# Simple_Motherboard.net
KiCad netlist of a schematic drawn in EAGLE
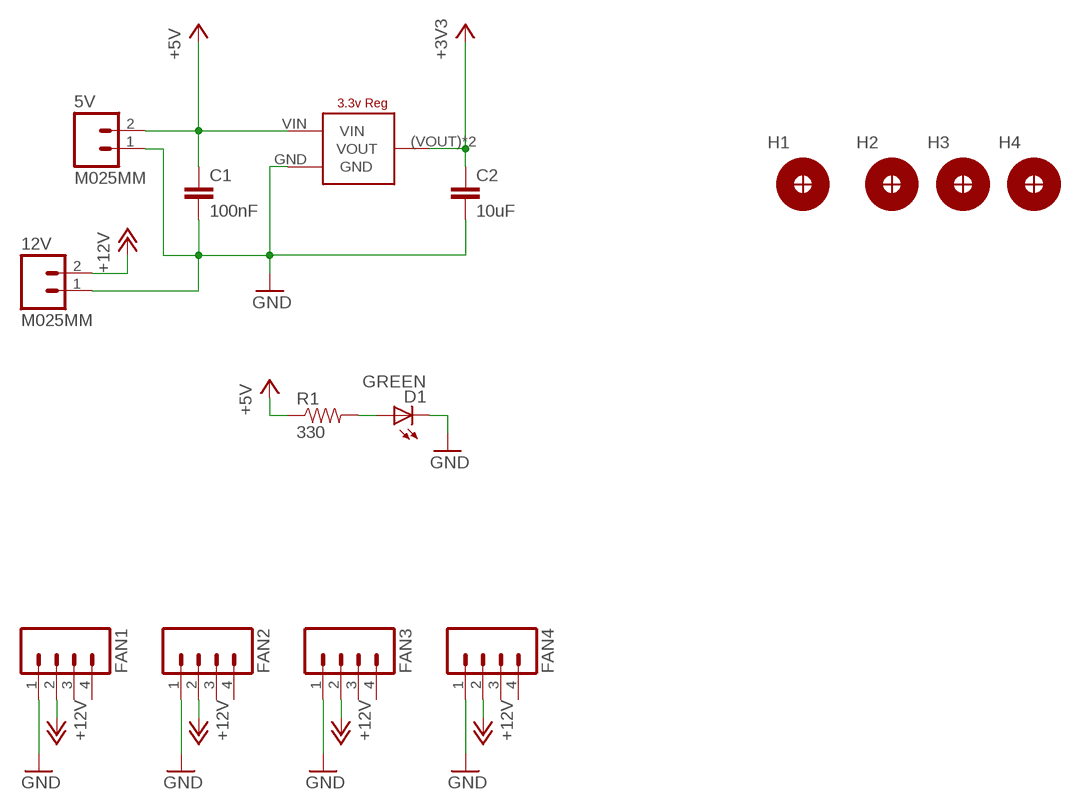
[diagram p0: schematic, sheet 1]
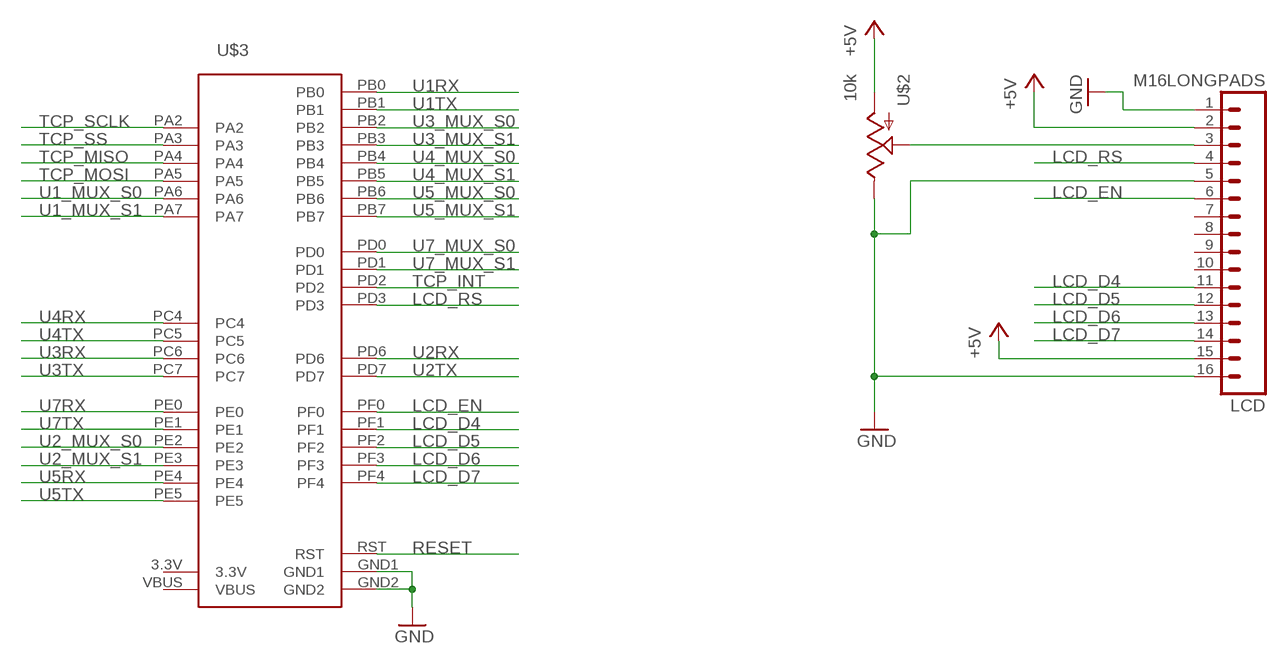
[diagram p1: schematic, sheet 2]
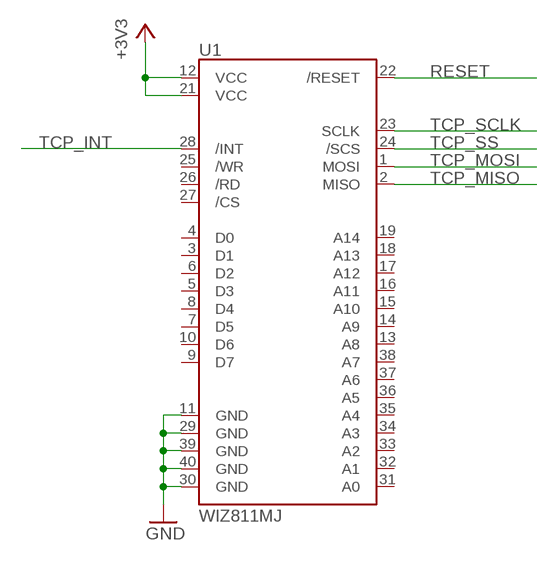
[diagram p2: schematic, sheet 3]
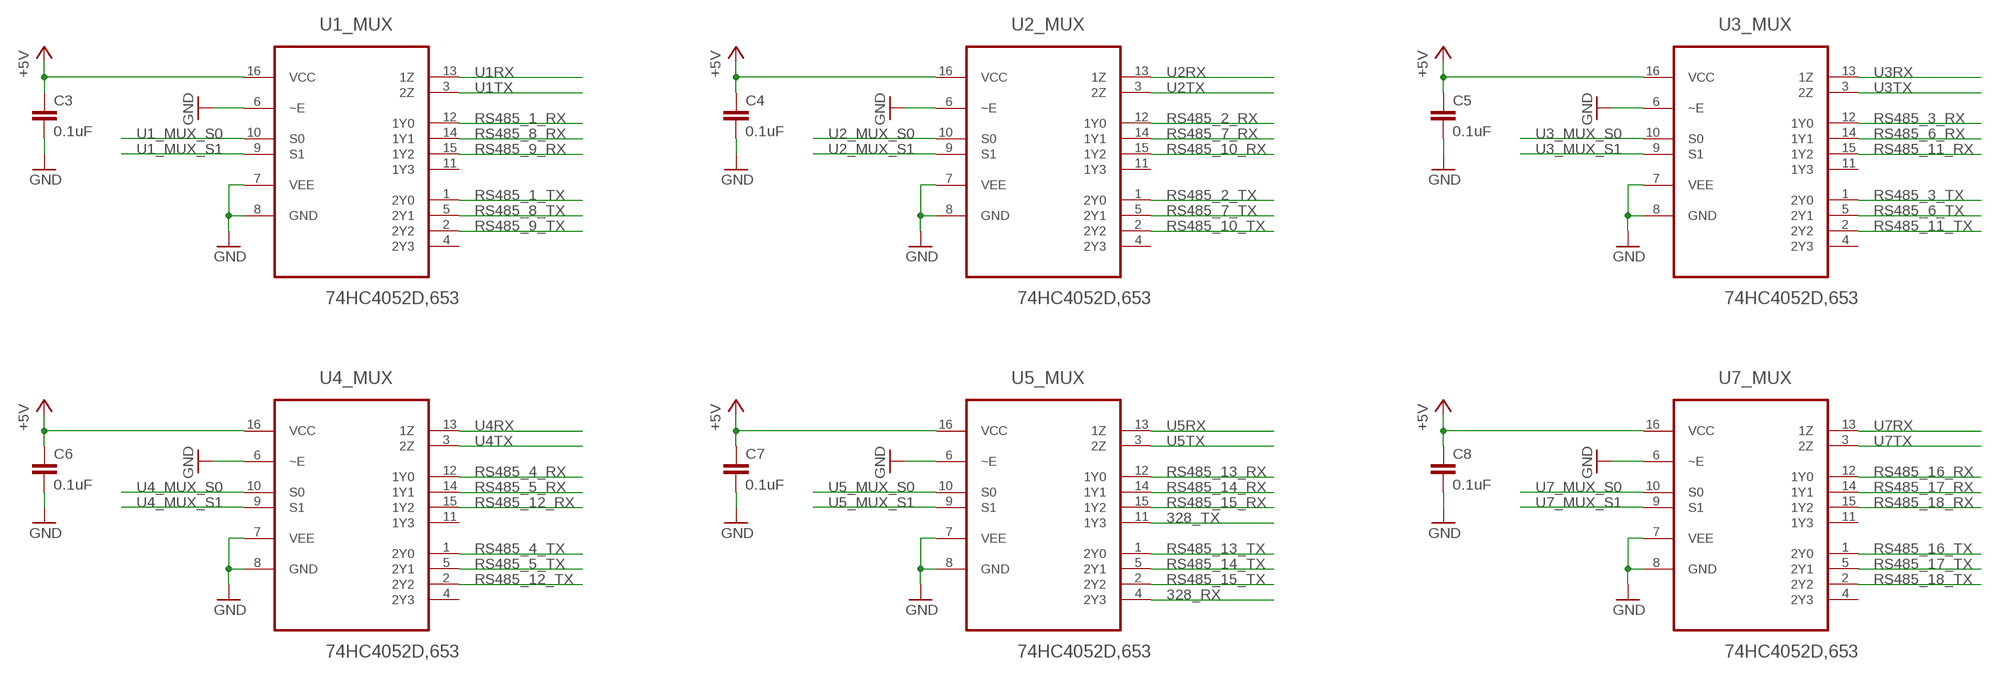
[diagram p3: schematic, sheet 4]
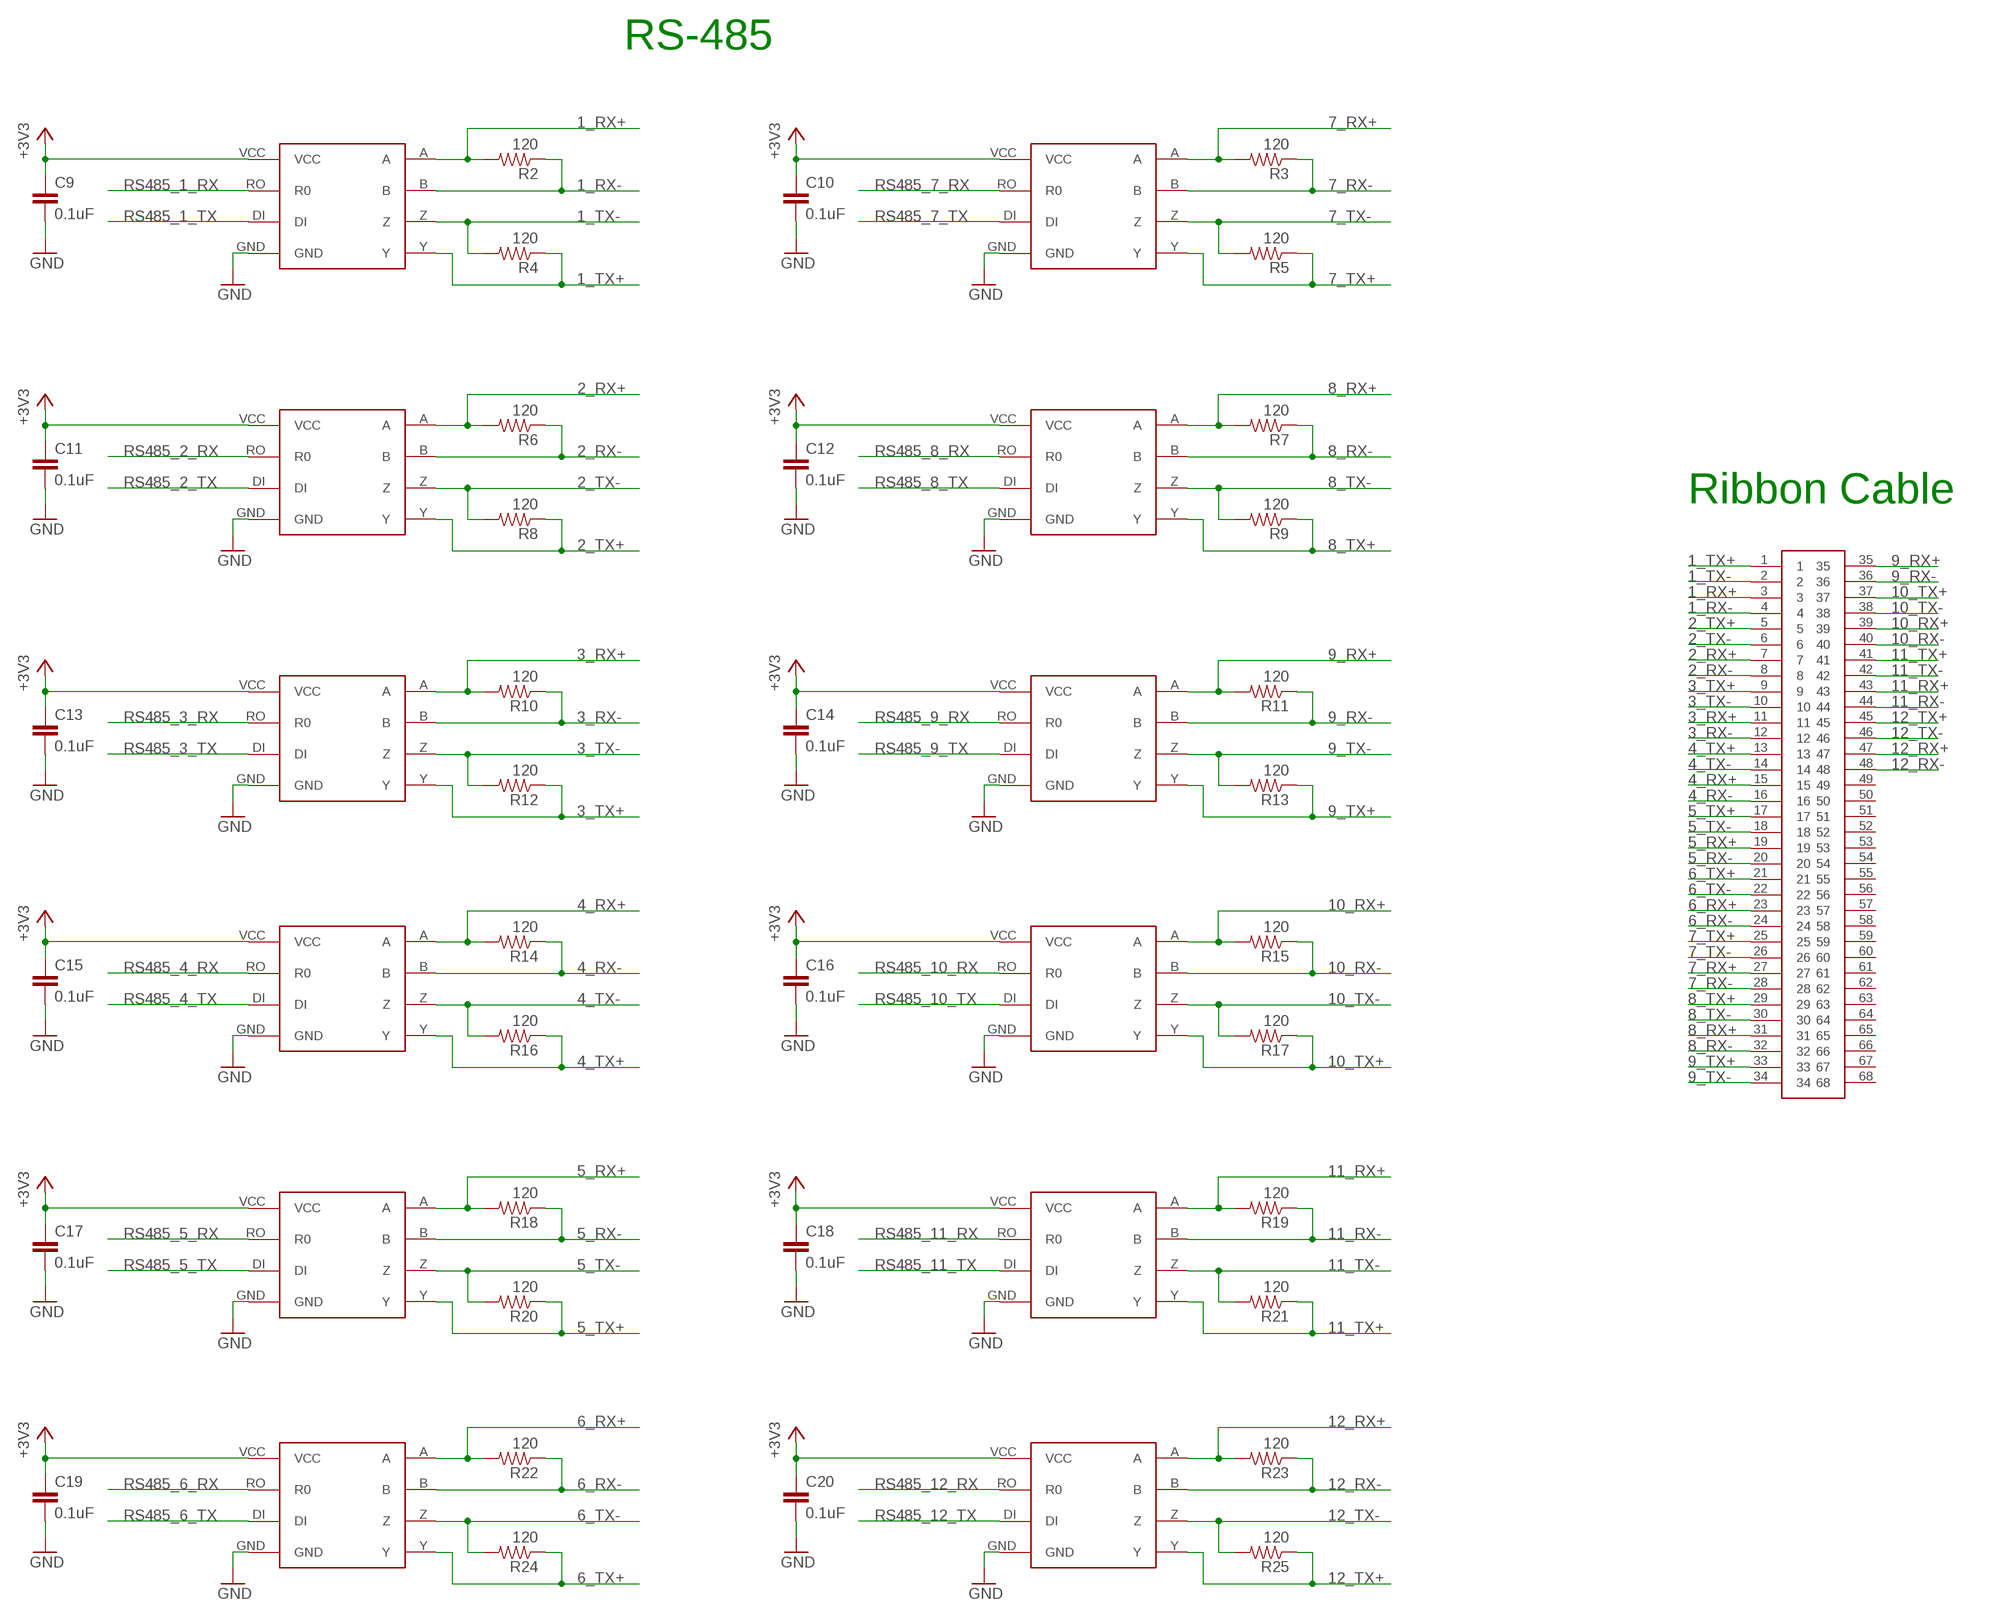
[diagram p4: schematic, sheet 5]
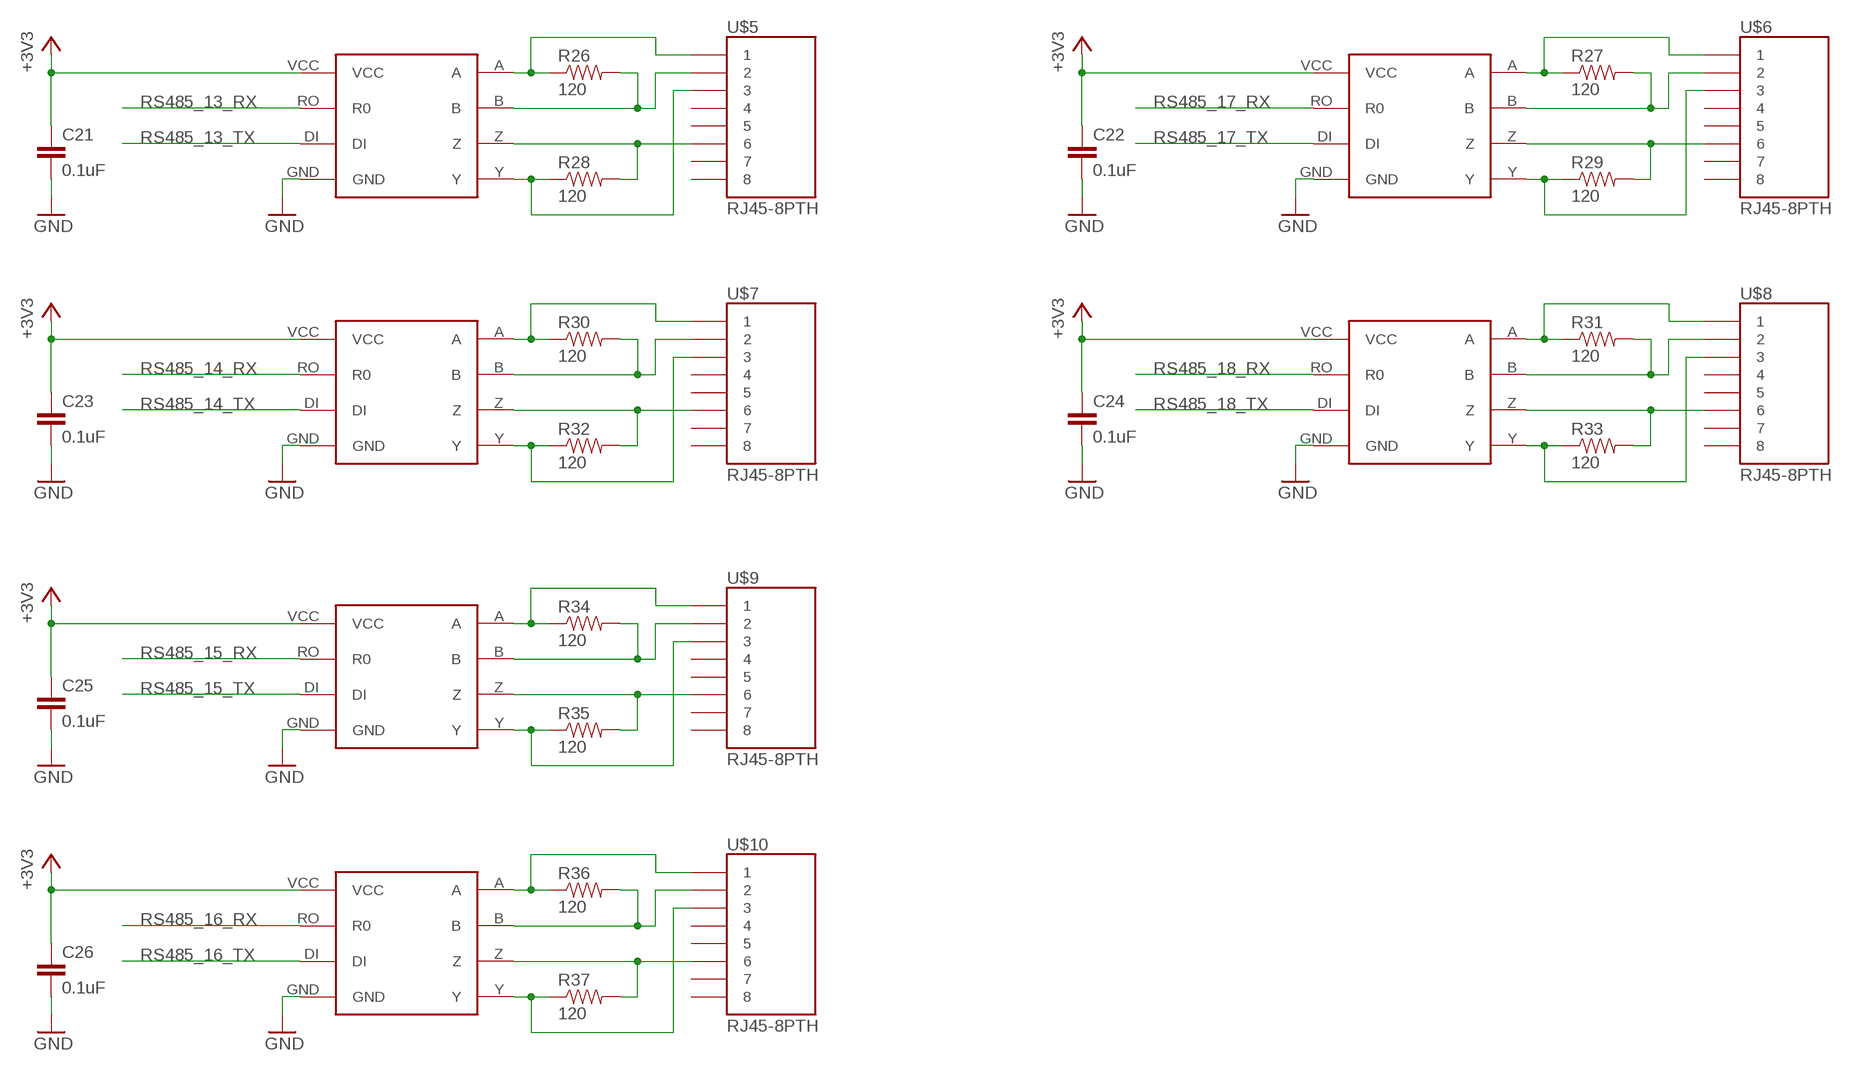
[diagram p5: schematic, sheet 6]
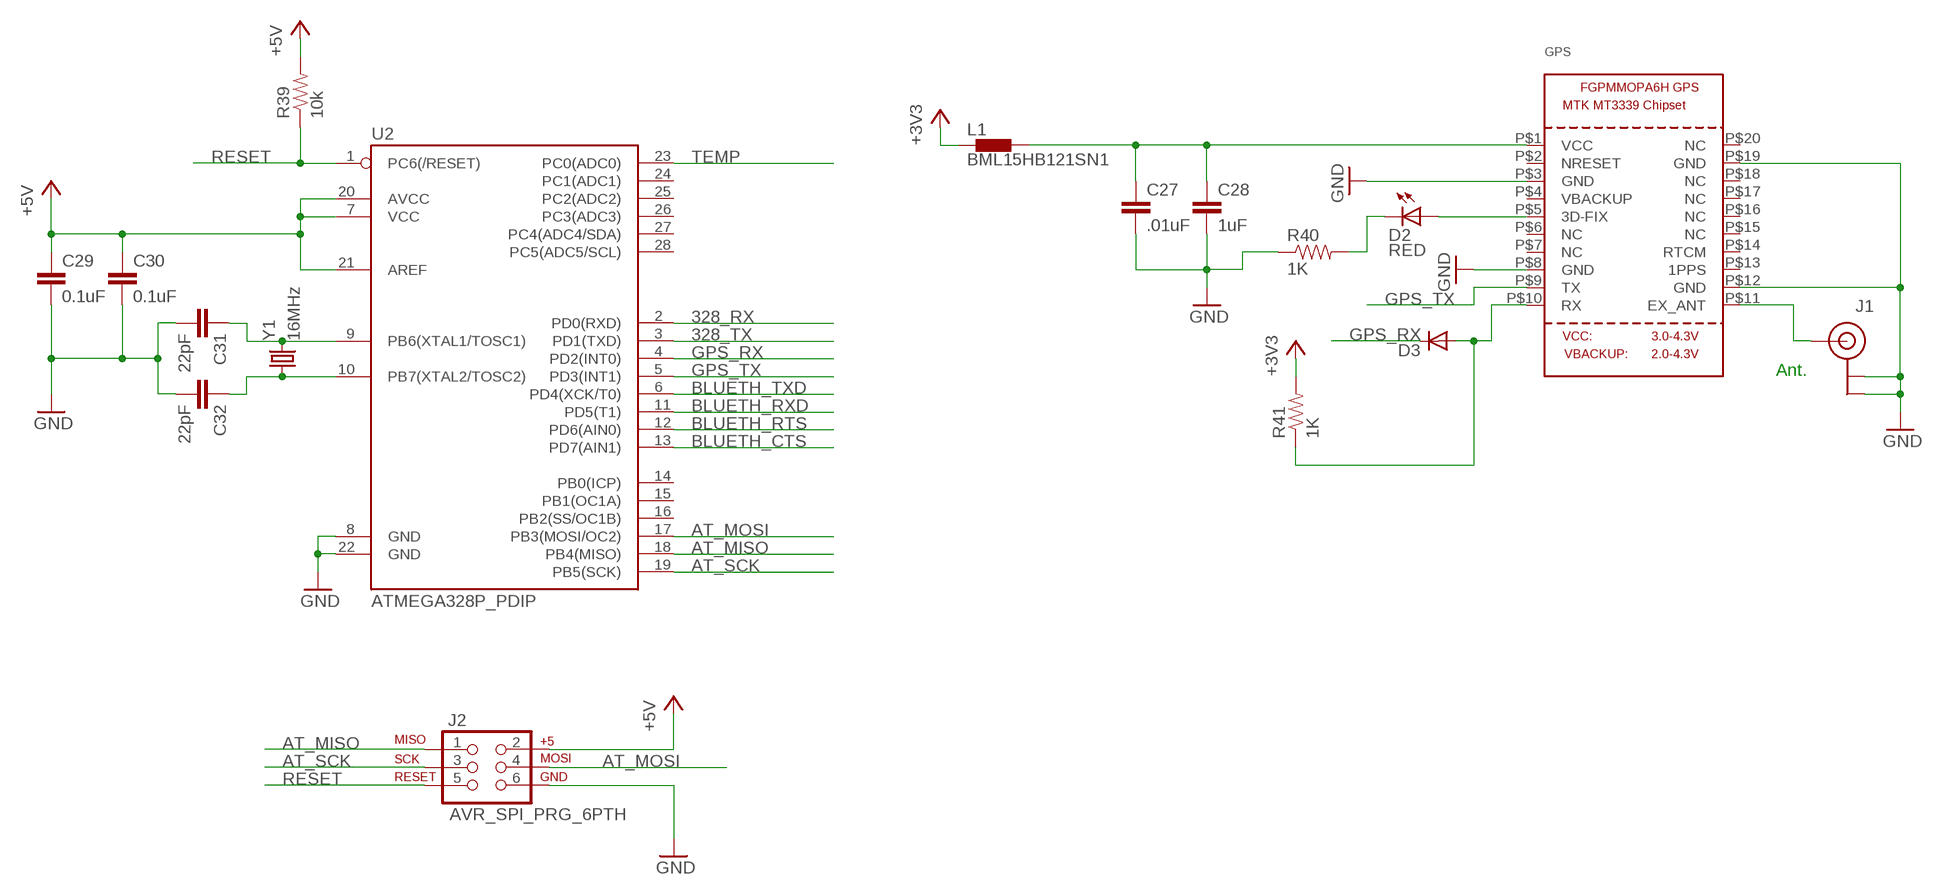
[diagram p6: schematic, sheet 7]

(export (version "E")
  (design (tool "Eeschema 10.0.6"))
  (components
    (comp (ref "C3")
      (value "0.1uF")
      (footprint "eagle-import:1206")
      (libsource (lib "eagle-import") (part "CAP1206"))
    )
    (comp (ref "C4")
      (value "0.1uF")
      (footprint "eagle-import:1206")
      (libsource (lib "eagle-import") (part "CAP1206"))
    )
    (comp (ref "C5")
      (value "0.1uF")
      (footprint "eagle-import:1206")
      (libsource (lib "eagle-import") (part "CAP1206"))
    )
    (comp (ref "C6")
      (value "0.1uF")
      (footprint "eagle-import:1206")
      (libsource (lib "eagle-import") (part "CAP1206"))
    )
    (comp (ref "C7")
      (value "0.1uF")
      (footprint "eagle-import:1206")
      (libsource (lib "eagle-import") (part "CAP1206"))
    )
    (comp (ref "C8")
      (value "0.1uF")
      (footprint "eagle-import:1206")
      (libsource (lib "eagle-import") (part "CAP1206"))
    )
    (comp (ref "U1_MUX")
      (value "74HC4052D,653")
      (footprint "eagle-import:SOIC127P600X175-16N")
      (libsource (lib "eagle-import") (part "74HC4052D,653"))
    )
    (comp (ref "U2_MUX")
      (value "74HC4052D,653")
      (footprint "eagle-import:SOIC127P600X175-16N")
      (libsource (lib "eagle-import") (part "74HC4052D,653"))
    )
    (comp (ref "U3_MUX")
      (value "74HC4052D,653")
      (footprint "eagle-import:SOIC127P600X175-16N")
      (libsource (lib "eagle-import") (part "74HC4052D,653"))
    )
    (comp (ref "U4_MUX")
      (value "74HC4052D,653")
      (footprint "eagle-import:SOIC127P600X175-16N")
      (libsource (lib "eagle-import") (part "74HC4052D,653"))
    )
    (comp (ref "U5_MUX")
      (value "74HC4052D,653")
      (footprint "eagle-import:SOIC127P600X175-16N")
      (libsource (lib "eagle-import") (part "74HC4052D,653"))
    )
    (comp (ref "U7_MUX")
      (value "74HC4052D,653")
      (footprint "eagle-import:SOIC127P600X175-16N")
      (libsource (lib "eagle-import") (part "74HC4052D,653"))
    )
    (comp (ref "LCD")
      (value "M16LONGPADS")
      (footprint "eagle-import:1X16_LONGPADS")
      (libsource (lib "eagle-import") (part "M16LONGPADS"))
    )
    (comp (ref "U$2")
      (value "10k")
      (footprint "eagle-import:3362U")
      (libsource (lib "eagle-import") (part "POT100K_3362U"))
    )
    (comp (ref "U$3")
      (value "STELLARIS-LAUNCHPADSTELLARIS-LAUNCHPAD-XL")
      (footprint "eagle-import:LAUNCHPAD-XL")
      (libsource (lib "eagle-import") (part "STELLARIS-LAUNCHPADSTELLARIS-LAUNCHPAD-XL"))
    )
    (comp (ref "U1")
      (value "WIZ811MJ")
      (footprint "eagle-import:WIZ811MJ")
      (libsource (lib "eagle-import") (part "WIZ811MJ"))
    )
    (comp (ref "C21")
      (value "0.1uF")
      (footprint "eagle-import:1206")
      (libsource (lib "eagle-import") (part "CAP1206"))
    )
    (comp (ref "C22")
      (value "0.1uF")
      (footprint "eagle-import:1206")
      (libsource (lib "eagle-import") (part "CAP1206"))
    )
    (comp (ref "C23")
      (value "0.1uF")
      (footprint "eagle-import:1206")
      (libsource (lib "eagle-import") (part "CAP1206"))
    )
    (comp (ref "C24")
      (value "0.1uF")
      (footprint "eagle-import:1206")
      (libsource (lib "eagle-import") (part "CAP1206"))
    )
    (comp (ref "C25")
      (value "0.1uF")
      (footprint "eagle-import:1206")
      (libsource (lib "eagle-import") (part "CAP1206"))
    )
    (comp (ref "C26")
      (value "0.1uF")
      (footprint "eagle-import:1206")
      (libsource (lib "eagle-import") (part "CAP1206"))
    )
    (comp (ref "R26")
      (value "120")
      (footprint "eagle-import:1206")
      (libsource (lib "eagle-import") (part "RESISTOR1206"))
    )
    (comp (ref "R27")
      (value "120")
      (footprint "eagle-import:1206")
      (libsource (lib "eagle-import") (part "RESISTOR1206"))
    )
    (comp (ref "R28")
      (value "120")
      (footprint "eagle-import:1206")
      (libsource (lib "eagle-import") (part "RESISTOR1206"))
    )
    (comp (ref "R29")
      (value "120")
      (footprint "eagle-import:1206")
      (libsource (lib "eagle-import") (part "RESISTOR1206"))
    )
    (comp (ref "R30")
      (value "120")
      (footprint "eagle-import:1206")
      (libsource (lib "eagle-import") (part "RESISTOR1206"))
    )
    (comp (ref "R31")
      (value "120")
      (footprint "eagle-import:1206")
      (libsource (lib "eagle-import") (part "RESISTOR1206"))
    )
    (comp (ref "R32")
      (value "120")
      (footprint "eagle-import:1206")
      (libsource (lib "eagle-import") (part "RESISTOR1206"))
    )
    (comp (ref "R33")
      (value "120")
      (footprint "eagle-import:1206")
      (libsource (lib "eagle-import") (part "RESISTOR1206"))
    )
    (comp (ref "R34")
      (value "120")
      (footprint "eagle-import:1206")
      (libsource (lib "eagle-import") (part "RESISTOR1206"))
    )
    (comp (ref "R35")
      (value "120")
      (footprint "eagle-import:1206")
      (libsource (lib "eagle-import") (part "RESISTOR1206"))
    )
    (comp (ref "R36")
      (value "120")
      (footprint "eagle-import:1206")
      (libsource (lib "eagle-import") (part "RESISTOR1206"))
    )
    (comp (ref "R37")
      (value "120")
      (footprint "eagle-import:1206")
      (libsource (lib "eagle-import") (part "RESISTOR1206"))
    )
    (comp (ref "RS-485-1")
      (value "MAX3077")
      (footprint "eagle-import:MAX3070E")
      (libsource (lib "eagle-import") (part "MAX3077"))
    )
    (comp (ref "RS-485-2")
      (value "MAX3077")
      (footprint "eagle-import:MAX3070E")
      (libsource (lib "eagle-import") (part "MAX3077"))
    )
    (comp (ref "RS-485-3")
      (value "MAX3077")
      (footprint "eagle-import:MAX3070E")
      (libsource (lib "eagle-import") (part "MAX3077"))
    )
    (comp (ref "RS-485-4")
      (value "MAX3077")
      (footprint "eagle-import:MAX3070E")
      (libsource (lib "eagle-import") (part "MAX3077"))
    )
    (comp (ref "RS-485-5")
      (value "MAX3077")
      (footprint "eagle-import:MAX3070E")
      (libsource (lib "eagle-import") (part "MAX3077"))
    )
    (comp (ref "RS-485-6")
      (value "MAX3077")
      (footprint "eagle-import:MAX3070E")
      (libsource (lib "eagle-import") (part "MAX3077"))
    )
    (comp (ref "U$5")
      (value "RJ45-8PTH")
      (footprint "eagle-import:RJ45-8")
      (libsource (lib "eagle-import") (part "RJ45-8PTH"))
    )
    (comp (ref "U$6")
      (value "RJ45-8PTH")
      (footprint "eagle-import:RJ45-8")
      (libsource (lib "eagle-import") (part "RJ45-8PTH"))
    )
    (comp (ref "U$7")
      (value "RJ45-8PTH")
      (footprint "eagle-import:RJ45-8")
      (libsource (lib "eagle-import") (part "RJ45-8PTH"))
    )
    (comp (ref "U$8")
      (value "RJ45-8PTH")
      (footprint "eagle-import:RJ45-8")
      (libsource (lib "eagle-import") (part "RJ45-8PTH"))
    )
    (comp (ref "U$9")
      (value "RJ45-8PTH")
      (footprint "eagle-import:RJ45-8")
      (libsource (lib "eagle-import") (part "RJ45-8PTH"))
    )
    (comp (ref "U$10")
      (value "RJ45-8PTH")
      (footprint "eagle-import:RJ45-8")
      (libsource (lib "eagle-import") (part "RJ45-8PTH"))
    )
    (comp (ref "C9")
      (value "0.1uF")
      (footprint "eagle-import:1206")
      (libsource (lib "eagle-import") (part "CAP1206"))
    )
    (comp (ref "C10")
      (value "0.1uF")
      (footprint "eagle-import:1206")
      (libsource (lib "eagle-import") (part "CAP1206"))
    )
    (comp (ref "C11")
      (value "0.1uF")
      (footprint "eagle-import:1206")
      (libsource (lib "eagle-import") (part "CAP1206"))
    )
    (comp (ref "C12")
      (value "0.1uF")
      (footprint "eagle-import:1206")
      (libsource (lib "eagle-import") (part "CAP1206"))
    )
    (comp (ref "C13")
      (value "0.1uF")
      (footprint "eagle-import:1206")
      (libsource (lib "eagle-import") (part "CAP1206"))
    )
    (comp (ref "C14")
      (value "0.1uF")
      (footprint "eagle-import:1206")
      (libsource (lib "eagle-import") (part "CAP1206"))
    )
    (comp (ref "C15")
      (value "0.1uF")
      (footprint "eagle-import:1206")
      (libsource (lib "eagle-import") (part "CAP1206"))
    )
    (comp (ref "C16")
      (value "0.1uF")
      (footprint "eagle-import:1206")
      (libsource (lib "eagle-import") (part "CAP1206"))
    )
    (comp (ref "C17")
      (value "0.1uF")
      (footprint "eagle-import:1206")
      (libsource (lib "eagle-import") (part "CAP1206"))
    )
    (comp (ref "C18")
      (value "0.1uF")
      (footprint "eagle-import:1206")
      (libsource (lib "eagle-import") (part "CAP1206"))
    )
    (comp (ref "C19")
      (value "0.1uF")
      (footprint "eagle-import:1206")
      (libsource (lib "eagle-import") (part "CAP1206"))
    )
    (comp (ref "C20")
      (value "0.1uF")
      (footprint "eagle-import:1206")
      (libsource (lib "eagle-import") (part "CAP1206"))
    )
    (comp (ref "R2")
      (value "120")
      (footprint "eagle-import:1206")
      (libsource (lib "eagle-import") (part "RESISTOR1206"))
    )
    (comp (ref "R3")
      (value "120")
      (footprint "eagle-import:1206")
      (libsource (lib "eagle-import") (part "RESISTOR1206"))
    )
    (comp (ref "R4")
      (value "120")
      (footprint "eagle-import:1206")
      (libsource (lib "eagle-import") (part "RESISTOR1206"))
    )
    (comp (ref "R5")
      (value "120")
      (footprint "eagle-import:1206")
      (libsource (lib "eagle-import") (part "RESISTOR1206"))
    )
    (comp (ref "R6")
      (value "120")
      (footprint "eagle-import:1206")
      (libsource (lib "eagle-import") (part "RESISTOR1206"))
    )
    (comp (ref "R7")
      (value "120")
      (footprint "eagle-import:1206")
      (libsource (lib "eagle-import") (part "RESISTOR1206"))
    )
    (comp (ref "R8")
      (value "120")
      (footprint "eagle-import:1206")
      (libsource (lib "eagle-import") (part "RESISTOR1206"))
    )
    (comp (ref "R9")
      (value "120")
      (footprint "eagle-import:1206")
      (libsource (lib "eagle-import") (part "RESISTOR1206"))
    )
    (comp (ref "R10")
      (value "120")
      (footprint "eagle-import:1206")
      (libsource (lib "eagle-import") (part "RESISTOR1206"))
    )
    (comp (ref "R11")
      (value "120")
      (footprint "eagle-import:1206")
      (libsource (lib "eagle-import") (part "RESISTOR1206"))
    )
    (comp (ref "R12")
      (value "120")
      (footprint "eagle-import:1206")
      (libsource (lib "eagle-import") (part "RESISTOR1206"))
    )
    (comp (ref "R13")
      (value "120")
      (footprint "eagle-import:1206")
      (libsource (lib "eagle-import") (part "RESISTOR1206"))
    )
    (comp (ref "R14")
      (value "120")
      (footprint "eagle-import:1206")
      (libsource (lib "eagle-import") (part "RESISTOR1206"))
    )
    (comp (ref "R15")
      (value "120")
      (footprint "eagle-import:1206")
      (libsource (lib "eagle-import") (part "RESISTOR1206"))
    )
    (comp (ref "R16")
      (value "120")
      (footprint "eagle-import:1206")
      (libsource (lib "eagle-import") (part "RESISTOR1206"))
    )
    (comp (ref "R17")
      (value "120")
      (footprint "eagle-import:1206")
      (libsource (lib "eagle-import") (part "RESISTOR1206"))
    )
    (comp (ref "R18")
      (value "120")
      (footprint "eagle-import:1206")
      (libsource (lib "eagle-import") (part "RESISTOR1206"))
    )
    (comp (ref "R19")
      (value "120")
      (footprint "eagle-import:1206")
      (libsource (lib "eagle-import") (part "RESISTOR1206"))
    )
    (comp (ref "R20")
      (value "120")
      (footprint "eagle-import:1206")
      (libsource (lib "eagle-import") (part "RESISTOR1206"))
    )
    (comp (ref "R21")
      (value "120")
      (footprint "eagle-import:1206")
      (libsource (lib "eagle-import") (part "RESISTOR1206"))
    )
    (comp (ref "R22")
      (value "120")
      (footprint "eagle-import:1206")
      (libsource (lib "eagle-import") (part "RESISTOR1206"))
    )
    (comp (ref "R23")
      (value "120")
      (footprint "eagle-import:1206")
      (libsource (lib "eagle-import") (part "RESISTOR1206"))
    )
    (comp (ref "R24")
      (value "120")
      (footprint "eagle-import:1206")
      (libsource (lib "eagle-import") (part "RESISTOR1206"))
    )
    (comp (ref "R25")
      (value "120")
      (footprint "eagle-import:1206")
      (libsource (lib "eagle-import") (part "RESISTOR1206"))
    )
    (comp (ref "RS_TRANS_1")
      (value "MAX3077")
      (footprint "eagle-import:MAX3070E")
      (libsource (lib "eagle-import") (part "MAX3077"))
    )
    (comp (ref "RS_TRANS_2")
      (value "MAX3077")
      (footprint "eagle-import:MAX3070E")
      (libsource (lib "eagle-import") (part "MAX3077"))
    )
    (comp (ref "RS_TRANS_3")
      (value "MAX3077")
      (footprint "eagle-import:MAX3070E")
      (libsource (lib "eagle-import") (part "MAX3077"))
    )
    (comp (ref "RS_TRANS_4")
      (value "MAX3077")
      (footprint "eagle-import:MAX3070E")
      (libsource (lib "eagle-import") (part "MAX3077"))
    )
    (comp (ref "RS_TRANS_5")
      (value "MAX3077")
      (footprint "eagle-import:MAX3070E")
      (libsource (lib "eagle-import") (part "MAX3077"))
    )
    (comp (ref "RS_TRANS_6")
      (value "MAX3077")
      (footprint "eagle-import:MAX3070E")
      (libsource (lib "eagle-import") (part "MAX3077"))
    )
    (comp (ref "RS_TRANS_7")
      (value "MAX3077")
      (footprint "eagle-import:MAX3070E")
      (libsource (lib "eagle-import") (part "MAX3077"))
    )
    (comp (ref "RS_TRANS_8")
      (value "MAX3077")
      (footprint "eagle-import:MAX3070E")
      (libsource (lib "eagle-import") (part "MAX3077"))
    )
    (comp (ref "RS_TRANS_9")
      (value "MAX3077")
      (footprint "eagle-import:MAX3070E")
      (libsource (lib "eagle-import") (part "MAX3077"))
    )
    (comp (ref "RS_TRANS_10")
      (value "MAX3077")
      (footprint "eagle-import:MAX3070E")
      (libsource (lib "eagle-import") (part "MAX3077"))
    )
    (comp (ref "RS_TRANS_11")
      (value "MAX3077")
      (footprint "eagle-import:MAX3070E")
      (libsource (lib "eagle-import") (part "MAX3077"))
    )
    (comp (ref "RS_TRANS_12")
      (value "MAX3077")
      (footprint "eagle-import:MAX3070E")
      (libsource (lib "eagle-import") (part "MAX3077"))
    )
    (comp (ref "U$4")
      (value "TB60050685100")
      (footprint "eagle-import:60050685100")
      (libsource (lib "eagle-import") (part "TB60050685100"))
    )
    (comp (ref "5V")
      (value "M025MM")
      (footprint "eagle-import:SCREWTERMINAL-5MM-2")
      (libsource (lib "eagle-import") (part "M025MM"))
    )
    (comp (ref "12V")
      (value "M025MM")
      (footprint "eagle-import:SCREWTERMINAL-5MM-2")
      (libsource (lib "eagle-import") (part "M025MM"))
    )
    (comp (ref "C1")
      (value "100nF")
      (footprint "eagle-import:1206")
      (libsource (lib "eagle-import") (part "CAP1206"))
    )
    (comp (ref "C2")
      (value "10uF")
      (footprint "eagle-import:1206")
      (libsource (lib "eagle-import") (part "CAP1206"))
    )
    (comp (ref "D1")
      (value "GREEN")
      (footprint "eagle-import:LED-1206")
      (libsource (lib "eagle-import") (part "LED-GREENLARGE"))
    )
    (comp (ref "FAN1")
      (value "M04LONGPADS")
      (footprint "eagle-import:1X04_LONGPADS")
      (libsource (lib "eagle-import") (part "M04LONGPADS"))
    )
    (comp (ref "FAN2")
      (value "M04LONGPADS")
      (footprint "eagle-import:1X04_LONGPADS")
      (libsource (lib "eagle-import") (part "M04LONGPADS"))
    )
    (comp (ref "FAN3")
      (value "M04LONGPADS")
      (footprint "eagle-import:1X04_LONGPADS")
      (libsource (lib "eagle-import") (part "M04LONGPADS"))
    )
    (comp (ref "FAN4")
      (value "M04LONGPADS")
      (footprint "eagle-import:1X04_LONGPADS")
      (libsource (lib "eagle-import") (part "M04LONGPADS"))
    )
    (comp (ref "H1")
      (value "H_MNTHOLE_#4")
      (footprint "eagle-import:H_MNTHOLE_#4")
      (libsource (lib "eagle-import") (part "H_MNTHOLE_#4"))
    )
    (comp (ref "H2")
      (value "H_MNTHOLE_#4")
      (footprint "eagle-import:H_MNTHOLE_#4")
      (libsource (lib "eagle-import") (part "H_MNTHOLE_#4"))
    )
    (comp (ref "H3")
      (value "H_MNTHOLE_#4")
      (footprint "eagle-import:H_MNTHOLE_#4")
      (libsource (lib "eagle-import") (part "H_MNTHOLE_#4"))
    )
    (comp (ref "H4")
      (value "H_MNTHOLE_#4")
      (footprint "eagle-import:H_MNTHOLE_#4")
      (libsource (lib "eagle-import") (part "H_MNTHOLE_#4"))
    )
    (comp (ref "R1")
      (value "330")
      (footprint "eagle-import:1206")
      (libsource (lib "eagle-import") (part "RESISTOR1206"))
    )
    (comp (ref "U$1")
      (value "LD1117")
      (footprint "eagle-import:LD1117SOT-223")
      (libsource (lib "eagle-import") (part "LD1117"))
    )
    (comp (ref "C27")
      (value ".01uF")
      (footprint "eagle-import:1206")
      (libsource (lib "eagle-import") (part "CAP1206"))
    )
    (comp (ref "C28")
      (value "1uF")
      (footprint "eagle-import:1206")
      (libsource (lib "eagle-import") (part "CAP1206"))
    )
    (comp (ref "C29")
      (value "0.1uF")
      (footprint "eagle-import:1206")
      (libsource (lib "eagle-import") (part "CAP1206"))
    )
    (comp (ref "C30")
      (value "0.1uF")
      (footprint "eagle-import:1206")
      (libsource (lib "eagle-import") (part "CAP1206"))
    )
    (comp (ref "C31")
      (value "22pF")
      (footprint "eagle-import:1206")
      (libsource (lib "eagle-import") (part "CAP1206"))
    )
    (comp (ref "C32")
      (value "22pF")
      (footprint "eagle-import:1206")
      (libsource (lib "eagle-import") (part "CAP1206"))
    )
    (comp (ref "D2")
      (value "RED")
      (footprint "eagle-import:LED-1206")
      (libsource (lib "eagle-import") (part "LED-RED1206"))
    )
    (comp (ref "D3")
      (value "DIODEHV")
      (footprint "eagle-import:DIODE-HV")
      (libsource (lib "eagle-import") (part "DIODEHV"))
    )
    (comp (ref "GPS")
      (value "GPS_FGPMMOPA6H")
      (footprint "eagle-import:FGPMMOPA6H")
      (libsource (lib "eagle-import") (part "GPS_FGPMMOPA6H"))
    )
    (comp (ref "J1")
      (value "U.FL")
      (footprint "eagle-import:U.FL")
      (libsource (lib "eagle-import") (part "U.FL"))
    )
    (comp (ref "J2")
      (value "AVR_SPI_PRG_6PTH")
      (footprint "eagle-import:2X3")
      (libsource (lib "eagle-import") (part "AVR_SPI_PRG_6PTH"))
    )
    (comp (ref "L1")
      (value "BML15HB121SN1")
      (footprint "eagle-import:0402")
      (libsource (lib "eagle-import") (part "BML15HB121SN1"))
    )
    (comp (ref "R39")
      (value "10k")
      (footprint "eagle-import:1206")
      (libsource (lib "eagle-import") (part "SparkFun-Resistors_RESISTOR1206"))
    )
    (comp (ref "R40")
      (value "1K")
      (footprint "eagle-import:1206")
      (libsource (lib "eagle-import") (part "RESISTOR1206"))
    )
    (comp (ref "R41")
      (value "1K")
      (footprint "eagle-import:1206")
      (libsource (lib "eagle-import") (part "RESISTOR1206"))
    )
    (comp (ref "U2")
      (value "ATMEGA328P_PDIP")
      (footprint "eagle-import:DIL28-3")
      (libsource (lib "eagle-import") (part "ATMEGA328P_PDIP"))
    )
    (comp (ref "Y1")
      (value "16MHz")
      (footprint "eagle-import:HC49US")
      (libsource (lib "eagle-import") (part "CRYSTALHC49US"))
    )
  )
  (nets
    (net (code "1") (name "+3V3") (class "Default")
      (node (ref "C10") (pin "1") (pinfunction "1_1") (pintype "passive"))
      (node (ref "C11") (pin "1") (pinfunction "1_1") (pintype "passive"))
      (node (ref "C12") (pin "1") (pinfunction "1_1") (pintype "passive"))
      (node (ref "C13") (pin "1") (pinfunction "1_1") (pintype "passive"))
      (node (ref "C14") (pin "1") (pinfunction "1_1") (pintype "passive"))
      (node (ref "C15") (pin "1") (pinfunction "1_1") (pintype "passive"))
      (node (ref "C16") (pin "1") (pinfunction "1_1") (pintype "passive"))
      (node (ref "C17") (pin "1") (pinfunction "1_1") (pintype "passive"))
      (node (ref "C18") (pin "1") (pinfunction "1_1") (pintype "passive"))
      (node (ref "C19") (pin "1") (pinfunction "1_1") (pintype "passive"))
      (node (ref "C2") (pin "1") (pinfunction "1_1") (pintype "passive"))
      (node (ref "C20") (pin "1") (pinfunction "1_1") (pintype "passive"))
      (node (ref "C21") (pin "1") (pinfunction "1_1") (pintype "passive"))
      (node (ref "C22") (pin "1") (pinfunction "1_1") (pintype "passive"))
      (node (ref "C23") (pin "1") (pinfunction "1_1") (pintype "passive"))
      (node (ref "C24") (pin "1") (pinfunction "1_1") (pintype "passive"))
      (node (ref "C25") (pin "1") (pinfunction "1_1") (pintype "passive"))
      (node (ref "C26") (pin "1") (pinfunction "1_1") (pintype "passive"))
      (node (ref "C9") (pin "1") (pinfunction "1_1") (pintype "passive"))
      (node (ref "L1") (pin "1") (pinfunction "1_1") (pintype "passive"))
      (node (ref "R41") (pin "2") (pinfunction "2_2") (pintype "passive"))
      (node (ref "RS-485-1") (pin "VCC") (pinfunction "VCC_VCC") (pintype "bidirectional"))
      (node (ref "RS-485-2") (pin "VCC") (pinfunction "VCC_VCC") (pintype "bidirectional"))
      (node (ref "RS-485-3") (pin "VCC") (pinfunction "VCC_VCC") (pintype "bidirectional"))
      (node (ref "RS-485-4") (pin "VCC") (pinfunction "VCC_VCC") (pintype "bidirectional"))
      (node (ref "RS-485-5") (pin "VCC") (pinfunction "VCC_VCC") (pintype "bidirectional"))
      (node (ref "RS-485-6") (pin "VCC") (pinfunction "VCC_VCC") (pintype "bidirectional"))
      (node (ref "RS_TRANS_1") (pin "VCC") (pinfunction "VCC_VCC") (pintype "bidirectional"))
      (node (ref "RS_TRANS_10") (pin "VCC") (pinfunction "VCC_VCC") (pintype "bidirectional"))
      (node (ref "RS_TRANS_11") (pin "VCC") (pinfunction "VCC_VCC") (pintype "bidirectional"))
      (node (ref "RS_TRANS_12") (pin "VCC") (pinfunction "VCC_VCC") (pintype "bidirectional"))
      (node (ref "RS_TRANS_2") (pin "VCC") (pinfunction "VCC_VCC") (pintype "bidirectional"))
      (node (ref "RS_TRANS_3") (pin "VCC") (pinfunction "VCC_VCC") (pintype "bidirectional"))
      (node (ref "RS_TRANS_4") (pin "VCC") (pinfunction "VCC_VCC") (pintype "bidirectional"))
      (node (ref "RS_TRANS_5") (pin "VCC") (pinfunction "VCC_VCC") (pintype "bidirectional"))
      (node (ref "RS_TRANS_6") (pin "VCC") (pinfunction "VCC_VCC") (pintype "bidirectional"))
      (node (ref "RS_TRANS_7") (pin "VCC") (pinfunction "VCC_VCC") (pintype "bidirectional"))
      (node (ref "RS_TRANS_8") (pin "VCC") (pinfunction "VCC_VCC") (pintype "bidirectional"))
      (node (ref "RS_TRANS_9") (pin "VCC") (pinfunction "VCC_VCC") (pintype "bidirectional"))
      (node (ref "U$1") (pin "(VOUT)") (pinfunction "VOUT_(VOUT)") (pintype "bidirectional"))
      (node (ref "U$1") (pin "VOUT") (pinfunction "VOUT_VOUT") (pintype "bidirectional"))
      (node (ref "U1") (pin "12") (pinfunction "VCC_12") (pintype "bidirectional"))
      (node (ref "U1") (pin "21") (pinfunction "VCC_21") (pintype "bidirectional"))
    )
    (net (code "2") (name "+5V") (class "Default")
      (node (ref "5V") (pin "2") (pinfunction "2_2") (pintype "passive"))
      (node (ref "C1") (pin "1") (pinfunction "1_1") (pintype "passive"))
      (node (ref "C29") (pin "1") (pinfunction "1_1") (pintype "passive"))
      (node (ref "C3") (pin "1") (pinfunction "1_1") (pintype "passive"))
      (node (ref "C30") (pin "1") (pinfunction "1_1") (pintype "passive"))
      (node (ref "C4") (pin "1") (pinfunction "1_1") (pintype "passive"))
      (node (ref "C5") (pin "1") (pinfunction "1_1") (pintype "passive"))
      (node (ref "C6") (pin "1") (pinfunction "1_1") (pintype "passive"))
      (node (ref "C7") (pin "1") (pinfunction "1_1") (pintype "passive"))
      (node (ref "C8") (pin "1") (pinfunction "1_1") (pintype "passive"))
      (node (ref "J2") (pin "2") (pinfunction "2_2") (pintype "passive"))
      (node (ref "LCD") (pin "15") (pinfunction "15_15") (pintype "passive"))
      (node (ref "LCD") (pin "2") (pinfunction "2_2") (pintype "passive"))
      (node (ref "R1") (pin "1") (pinfunction "1_1") (pintype "passive"))
      (node (ref "R39") (pin "2") (pinfunction "2_2") (pintype "passive"))
      (node (ref "U$1") (pin "VIN") (pinfunction "VIN_VIN") (pintype "bidirectional"))
      (node (ref "U$2") (pin "P$3") (pinfunction "A_P$3") (pintype "passive"))
      (node (ref "U1_MUX") (pin "16") (pinfunction "VCC_16") (pintype "power_in"))
      (node (ref "U2") (pin "20") (pinfunction "AVCC_20") (pintype "bidirectional"))
      (node (ref "U2") (pin "21") (pinfunction "AREF_21") (pintype "bidirectional"))
      (node (ref "U2") (pin "7") (pinfunction "VCC_7") (pintype "bidirectional"))
      (node (ref "U2_MUX") (pin "16") (pinfunction "VCC_16") (pintype "power_in"))
      (node (ref "U3_MUX") (pin "16") (pinfunction "VCC_16") (pintype "power_in"))
      (node (ref "U4_MUX") (pin "16") (pinfunction "VCC_16") (pintype "power_in"))
      (node (ref "U5_MUX") (pin "16") (pinfunction "VCC_16") (pintype "power_in"))
      (node (ref "U7_MUX") (pin "16") (pinfunction "VCC_16") (pintype "power_in"))
    )
    (net (code "3") (name "+12V") (class "Default")
      (node (ref "12V") (pin "2") (pinfunction "2_2") (pintype "passive"))
      (node (ref "FAN1") (pin "2") (pinfunction "2_2") (pintype "passive"))
      (node (ref "FAN2") (pin "2") (pinfunction "2_2") (pintype "passive"))
      (node (ref "FAN3") (pin "2") (pinfunction "2_2") (pintype "passive"))
      (node (ref "FAN4") (pin "2") (pinfunction "2_2") (pintype "passive"))
    )
    (net (code "4") (name "1_RX+") (class "Default")
      (node (ref "R2") (pin "2") (pinfunction "2_2") (pintype "passive"))
      (node (ref "RS_TRANS_1") (pin "A") (pinfunction "A_A") (pintype "bidirectional"))
      (node (ref "U$4") (pin "3") (pinfunction "3_3") (pintype "bidirectional"))
    )
    (net (code "5") (name "1_RX-") (class "Default")
      (node (ref "R2") (pin "1") (pinfunction "1_1") (pintype "passive"))
      (node (ref "RS_TRANS_1") (pin "B") (pinfunction "B_B") (pintype "bidirectional"))
      (node (ref "U$4") (pin "4") (pinfunction "4_4") (pintype "bidirectional"))
    )
    (net (code "6") (name "1_TX+") (class "Default")
      (node (ref "R4") (pin "1") (pinfunction "1_1") (pintype "passive"))
      (node (ref "RS_TRANS_1") (pin "Y") (pinfunction "Y_Y") (pintype "bidirectional"))
      (node (ref "U$4") (pin "1") (pinfunction "1_1") (pintype "bidirectional"))
    )
    (net (code "7") (name "1_TX-") (class "Default")
      (node (ref "R4") (pin "2") (pinfunction "2_2") (pintype "passive"))
      (node (ref "RS_TRANS_1") (pin "Z") (pinfunction "Z_Z") (pintype "bidirectional"))
      (node (ref "U$4") (pin "2") (pinfunction "2_2") (pintype "bidirectional"))
    )
    (net (code "8") (name "2_RX+") (class "Default")
      (node (ref "R6") (pin "2") (pinfunction "2_2") (pintype "passive"))
      (node (ref "RS_TRANS_3") (pin "A") (pinfunction "A_A") (pintype "bidirectional"))
      (node (ref "U$4") (pin "7") (pinfunction "7_7") (pintype "bidirectional"))
    )
    (net (code "9") (name "2_RX-") (class "Default")
      (node (ref "R6") (pin "1") (pinfunction "1_1") (pintype "passive"))
      (node (ref "RS_TRANS_3") (pin "B") (pinfunction "B_B") (pintype "bidirectional"))
      (node (ref "U$4") (pin "8") (pinfunction "8_8") (pintype "bidirectional"))
    )
    (net (code "10") (name "2_TX+") (class "Default")
      (node (ref "R8") (pin "1") (pinfunction "1_1") (pintype "passive"))
      (node (ref "RS_TRANS_3") (pin "Y") (pinfunction "Y_Y") (pintype "bidirectional"))
      (node (ref "U$4") (pin "5") (pinfunction "5_5") (pintype "bidirectional"))
    )
    (net (code "11") (name "2_TX-") (class "Default")
      (node (ref "R8") (pin "2") (pinfunction "2_2") (pintype "passive"))
      (node (ref "RS_TRANS_3") (pin "Z") (pinfunction "Z_Z") (pintype "bidirectional"))
      (node (ref "U$4") (pin "6") (pinfunction "6_6") (pintype "bidirectional"))
    )
    (net (code "12") (name "3.3V") (class "Default")
      (node (ref "U$3") (pin "3.3V") (pinfunction "3.3V_3.3V") (pintype "power_in"))
    )
    (net (code "13") (name "3_RX+") (class "Default")
      (node (ref "R10") (pin "2") (pinfunction "2_2") (pintype "passive"))
      (node (ref "RS_TRANS_5") (pin "A") (pinfunction "A_A") (pintype "bidirectional"))
      (node (ref "U$4") (pin "11") (pinfunction "11_11") (pintype "bidirectional"))
    )
    (net (code "14") (name "3_RX-") (class "Default")
      (node (ref "R10") (pin "1") (pinfunction "1_1") (pintype "passive"))
      (node (ref "RS_TRANS_5") (pin "B") (pinfunction "B_B") (pintype "bidirectional"))
      (node (ref "U$4") (pin "12") (pinfunction "12_12") (pintype "bidirectional"))
    )
    (net (code "15") (name "3_TX+") (class "Default")
      (node (ref "R12") (pin "1") (pinfunction "1_1") (pintype "passive"))
      (node (ref "RS_TRANS_5") (pin "Y") (pinfunction "Y_Y") (pintype "bidirectional"))
      (node (ref "U$4") (pin "9") (pinfunction "9_9") (pintype "bidirectional"))
    )
    (net (code "16") (name "3_TX-") (class "Default")
      (node (ref "R12") (pin "2") (pinfunction "2_2") (pintype "passive"))
      (node (ref "RS_TRANS_5") (pin "Z") (pinfunction "Z_Z") (pintype "bidirectional"))
      (node (ref "U$4") (pin "10") (pinfunction "10_10") (pintype "bidirectional"))
    )
    (net (code "17") (name "4_RX+") (class "Default")
      (node (ref "R14") (pin "2") (pinfunction "2_2") (pintype "passive"))
      (node (ref "RS_TRANS_7") (pin "A") (pinfunction "A_A") (pintype "bidirectional"))
      (node (ref "U$4") (pin "15") (pinfunction "15_15") (pintype "bidirectional"))
    )
    (net (code "18") (name "4_RX-") (class "Default")
      (node (ref "R14") (pin "1") (pinfunction "1_1") (pintype "passive"))
      (node (ref "RS_TRANS_7") (pin "B") (pinfunction "B_B") (pintype "bidirectional"))
      (node (ref "U$4") (pin "16") (pinfunction "16_16") (pintype "bidirectional"))
    )
    (net (code "19") (name "4_TX+") (class "Default")
      (node (ref "R16") (pin "1") (pinfunction "1_1") (pintype "passive"))
      (node (ref "RS_TRANS_7") (pin "Y") (pinfunction "Y_Y") (pintype "bidirectional"))
      (node (ref "U$4") (pin "13") (pinfunction "13_13") (pintype "bidirectional"))
    )
    (net (code "20") (name "4_TX-") (class "Default")
      (node (ref "R16") (pin "2") (pinfunction "2_2") (pintype "passive"))
      (node (ref "RS_TRANS_7") (pin "Z") (pinfunction "Z_Z") (pintype "bidirectional"))
      (node (ref "U$4") (pin "14") (pinfunction "14_14") (pintype "bidirectional"))
    )
    (net (code "21") (name "5_RX+") (class "Default")
      (node (ref "R18") (pin "2") (pinfunction "2_2") (pintype "passive"))
      (node (ref "RS_TRANS_9") (pin "A") (pinfunction "A_A") (pintype "bidirectional"))
      (node (ref "U$4") (pin "19") (pinfunction "19_19") (pintype "bidirectional"))
    )
    (net (code "22") (name "5_RX-") (class "Default")
      (node (ref "R18") (pin "1") (pinfunction "1_1") (pintype "passive"))
      (node (ref "RS_TRANS_9") (pin "B") (pinfunction "B_B") (pintype "bidirectional"))
      (node (ref "U$4") (pin "20") (pinfunction "20_20") (pintype "bidirectional"))
    )
    (net (code "23") (name "5_TX+") (class "Default")
      (node (ref "R20") (pin "1") (pinfunction "1_1") (pintype "passive"))
      (node (ref "RS_TRANS_9") (pin "Y") (pinfunction "Y_Y") (pintype "bidirectional"))
      (node (ref "U$4") (pin "17") (pinfunction "17_17") (pintype "bidirectional"))
    )
    (net (code "24") (name "5_TX-") (class "Default")
      (node (ref "R20") (pin "2") (pinfunction "2_2") (pintype "passive"))
      (node (ref "RS_TRANS_9") (pin "Z") (pinfunction "Z_Z") (pintype "bidirectional"))
      (node (ref "U$4") (pin "18") (pinfunction "18_18") (pintype "bidirectional"))
    )
    (net (code "25") (name "6_RX+") (class "Default")
      (node (ref "R22") (pin "2") (pinfunction "2_2") (pintype "passive"))
      (node (ref "RS_TRANS_11") (pin "A") (pinfunction "A_A") (pintype "bidirectional"))
      (node (ref "U$4") (pin "23") (pinfunction "23_23") (pintype "bidirectional"))
    )
    (net (code "26") (name "6_RX-") (class "Default")
      (node (ref "R22") (pin "1") (pinfunction "1_1") (pintype "passive"))
      (node (ref "RS_TRANS_11") (pin "B") (pinfunction "B_B") (pintype "bidirectional"))
      (node (ref "U$4") (pin "24") (pinfunction "24_24") (pintype "bidirectional"))
    )
    (net (code "27") (name "6_TX+") (class "Default")
      (node (ref "R24") (pin "1") (pinfunction "1_1") (pintype "passive"))
      (node (ref "RS_TRANS_11") (pin "Y") (pinfunction "Y_Y") (pintype "bidirectional"))
      (node (ref "U$4") (pin "21") (pinfunction "21_21") (pintype "bidirectional"))
    )
    (net (code "28") (name "6_TX-") (class "Default")
      (node (ref "R24") (pin "2") (pinfunction "2_2") (pintype "passive"))
      (node (ref "RS_TRANS_11") (pin "Z") (pinfunction "Z_Z") (pintype "bidirectional"))
      (node (ref "U$4") (pin "22") (pinfunction "22_22") (pintype "bidirectional"))
    )
    (net (code "29") (name "7_RX+") (class "Default")
      (node (ref "R3") (pin "2") (pinfunction "2_2") (pintype "passive"))
      (node (ref "RS_TRANS_2") (pin "A") (pinfunction "A_A") (pintype "bidirectional"))
      (node (ref "U$4") (pin "27") (pinfunction "27_27") (pintype "bidirectional"))
    )
    (net (code "30") (name "7_RX-") (class "Default")
      (node (ref "R3") (pin "1") (pinfunction "1_1") (pintype "passive"))
      (node (ref "RS_TRANS_2") (pin "B") (pinfunction "B_B") (pintype "bidirectional"))
      (node (ref "U$4") (pin "28") (pinfunction "28_28") (pintype "bidirectional"))
    )
    (net (code "31") (name "7_TX+") (class "Default")
      (node (ref "R5") (pin "1") (pinfunction "1_1") (pintype "passive"))
      (node (ref "RS_TRANS_2") (pin "Y") (pinfunction "Y_Y") (pintype "bidirectional"))
      (node (ref "U$4") (pin "25") (pinfunction "25_25") (pintype "bidirectional"))
    )
    (net (code "32") (name "7_TX-") (class "Default")
      (node (ref "R5") (pin "2") (pinfunction "2_2") (pintype "passive"))
      (node (ref "RS_TRANS_2") (pin "Z") (pinfunction "Z_Z") (pintype "bidirectional"))
      (node (ref "U$4") (pin "26") (pinfunction "26_26") (pintype "bidirectional"))
    )
    (net (code "33") (name "8_RX+") (class "Default")
      (node (ref "R7") (pin "2") (pinfunction "2_2") (pintype "passive"))
      (node (ref "RS_TRANS_4") (pin "A") (pinfunction "A_A") (pintype "bidirectional"))
      (node (ref "U$4") (pin "31") (pinfunction "31_31") (pintype "bidirectional"))
    )
    (net (code "34") (name "8_RX-") (class "Default")
      (node (ref "R7") (pin "1") (pinfunction "1_1") (pintype "passive"))
      (node (ref "RS_TRANS_4") (pin "B") (pinfunction "B_B") (pintype "bidirectional"))
      (node (ref "U$4") (pin "32") (pinfunction "32_32") (pintype "bidirectional"))
    )
    (net (code "35") (name "8_TX+") (class "Default")
      (node (ref "R9") (pin "1") (pinfunction "1_1") (pintype "passive"))
      (node (ref "RS_TRANS_4") (pin "Y") (pinfunction "Y_Y") (pintype "bidirectional"))
      (node (ref "U$4") (pin "29") (pinfunction "29_29") (pintype "bidirectional"))
    )
    (net (code "36") (name "8_TX-") (class "Default")
      (node (ref "R9") (pin "2") (pinfunction "2_2") (pintype "passive"))
      (node (ref "RS_TRANS_4") (pin "Z") (pinfunction "Z_Z") (pintype "bidirectional"))
      (node (ref "U$4") (pin "30") (pinfunction "30_30") (pintype "bidirectional"))
    )
    (net (code "37") (name "9_RX+") (class "Default")
      (node (ref "R11") (pin "2") (pinfunction "2_2") (pintype "passive"))
      (node (ref "RS_TRANS_6") (pin "A") (pinfunction "A_A") (pintype "bidirectional"))
      (node (ref "U$4") (pin "35") (pinfunction "35_35") (pintype "bidirectional"))
    )
    (net (code "38") (name "9_RX-") (class "Default")
      (node (ref "R11") (pin "1") (pinfunction "1_1") (pintype "passive"))
      (node (ref "RS_TRANS_6") (pin "B") (pinfunction "B_B") (pintype "bidirectional"))
      (node (ref "U$4") (pin "36") (pinfunction "36_36") (pintype "bidirectional"))
    )
    (net (code "39") (name "9_TX+") (class "Default")
      (node (ref "R13") (pin "1") (pinfunction "1_1") (pintype "passive"))
      (node (ref "RS_TRANS_6") (pin "Y") (pinfunction "Y_Y") (pintype "bidirectional"))
      (node (ref "U$4") (pin "33") (pinfunction "33_33") (pintype "bidirectional"))
    )
    (net (code "40") (name "9_TX-") (class "Default")
      (node (ref "R13") (pin "2") (pinfunction "2_2") (pintype "passive"))
      (node (ref "RS_TRANS_6") (pin "Z") (pinfunction "Z_Z") (pintype "bidirectional"))
      (node (ref "U$4") (pin "34") (pinfunction "34_34") (pintype "bidirectional"))
    )
    (net (code "41") (name "10_RX+") (class "Default")
      (node (ref "R15") (pin "2") (pinfunction "2_2") (pintype "passive"))
      (node (ref "RS_TRANS_8") (pin "A") (pinfunction "A_A") (pintype "bidirectional"))
      (node (ref "U$4") (pin "39") (pinfunction "39_39") (pintype "bidirectional"))
    )
    (net (code "42") (name "10_RX-") (class "Default")
      (node (ref "R15") (pin "1") (pinfunction "1_1") (pintype "passive"))
      (node (ref "RS_TRANS_8") (pin "B") (pinfunction "B_B") (pintype "bidirectional"))
      (node (ref "U$4") (pin "40") (pinfunction "40_40") (pintype "bidirectional"))
    )
    (net (code "43") (name "10_TX+") (class "Default")
      (node (ref "R17") (pin "1") (pinfunction "1_1") (pintype "passive"))
      (node (ref "RS_TRANS_8") (pin "Y") (pinfunction "Y_Y") (pintype "bidirectional"))
      (node (ref "U$4") (pin "37") (pinfunction "37_37") (pintype "bidirectional"))
    )
    (net (code "44") (name "10_TX-") (class "Default")
      (node (ref "R17") (pin "2") (pinfunction "2_2") (pintype "passive"))
      (node (ref "RS_TRANS_8") (pin "Z") (pinfunction "Z_Z") (pintype "bidirectional"))
      (node (ref "U$4") (pin "38") (pinfunction "38_38") (pintype "bidirectional"))
    )
    (net (code "45") (name "11_RX+") (class "Default")
      (node (ref "R19") (pin "2") (pinfunction "2_2") (pintype "passive"))
      (node (ref "RS_TRANS_10") (pin "A") (pinfunction "A_A") (pintype "bidirectional"))
      (node (ref "U$4") (pin "43") (pinfunction "43_43") (pintype "bidirectional"))
    )
    (net (code "46") (name "11_RX-") (class "Default")
      (node (ref "R19") (pin "1") (pinfunction "1_1") (pintype "passive"))
      (node (ref "RS_TRANS_10") (pin "B") (pinfunction "B_B") (pintype "bidirectional"))
      (node (ref "U$4") (pin "44") (pinfunction "44_44") (pintype "bidirectional"))
    )
    (net (code "47") (name "11_TX+") (class "Default")
      (node (ref "R21") (pin "1") (pinfunction "1_1") (pintype "passive"))
      (node (ref "RS_TRANS_10") (pin "Y") (pinfunction "Y_Y") (pintype "bidirectional"))
      (node (ref "U$4") (pin "41") (pinfunction "41_41") (pintype "bidirectional"))
    )
    (net (code "48") (name "11_TX-") (class "Default")
      (node (ref "R21") (pin "2") (pinfunction "2_2") (pintype "passive"))
      (node (ref "RS_TRANS_10") (pin "Z") (pinfunction "Z_Z") (pintype "bidirectional"))
      (node (ref "U$4") (pin "42") (pinfunction "42_42") (pintype "bidirectional"))
    )
    (net (code "49") (name "12_RX+") (class "Default")
      (node (ref "R23") (pin "2") (pinfunction "2_2") (pintype "passive"))
      (node (ref "RS_TRANS_12") (pin "A") (pinfunction "A_A") (pintype "bidirectional"))
      (node (ref "U$4") (pin "47") (pinfunction "47_47") (pintype "bidirectional"))
    )
    (net (code "50") (name "12_RX-") (class "Default")
      (node (ref "R23") (pin "1") (pinfunction "1_1") (pintype "passive"))
      (node (ref "RS_TRANS_12") (pin "B") (pinfunction "B_B") (pintype "bidirectional"))
      (node (ref "U$4") (pin "48") (pinfunction "48_48") (pintype "bidirectional"))
    )
    (net (code "51") (name "12_TX+") (class "Default")
      (node (ref "R25") (pin "1") (pinfunction "1_1") (pintype "passive"))
      (node (ref "RS_TRANS_12") (pin "Y") (pinfunction "Y_Y") (pintype "bidirectional"))
      (node (ref "U$4") (pin "45") (pinfunction "45_45") (pintype "bidirectional"))
    )
    (net (code "52") (name "12_TX-") (class "Default")
      (node (ref "R25") (pin "2") (pinfunction "2_2") (pintype "passive"))
      (node (ref "RS_TRANS_12") (pin "Z") (pinfunction "Z_Z") (pintype "bidirectional"))
      (node (ref "U$4") (pin "46") (pinfunction "46_46") (pintype "bidirectional"))
    )
    (net (code "53") (name "328_RX") (class "Default")
      (node (ref "U2") (pin "2") (pinfunction "PD0(RXD)_2") (pintype "bidirectional"))
      (node (ref "U5_MUX") (pin "4") (pinfunction "2Y3_4") (pintype "bidirectional"))
    )
    (net (code "54") (name "328_TX") (class "Default")
      (node (ref "U2") (pin "3") (pinfunction "PD1(TXD)_3") (pintype "bidirectional"))
      (node (ref "U5_MUX") (pin "11") (pinfunction "1Y3_11") (pintype "bidirectional"))
    )
    (net (code "55") (name "AT_MISO") (class "Default")
      (node (ref "J2") (pin "1") (pinfunction "1_1") (pintype "passive"))
      (node (ref "U2") (pin "18") (pinfunction "PB4(MISO)_18") (pintype "bidirectional"))
    )
    (net (code "56") (name "AT_MOSI") (class "Default")
      (node (ref "J2") (pin "4") (pinfunction "4_4") (pintype "passive"))
      (node (ref "U2") (pin "17") (pinfunction "PB3(MOSI/OC2)_17") (pintype "bidirectional"))
    )
    (net (code "57") (name "AT_SCK") (class "Default")
      (node (ref "J2") (pin "3") (pinfunction "3_3") (pintype "passive"))
      (node (ref "U2") (pin "19") (pinfunction "PB5(SCK)_19") (pintype "bidirectional"))
    )
    (net (code "58") (name "BLUETH_CTS") (class "Default")
      (node (ref "U2") (pin "13") (pinfunction "PD7(AIN1)_13") (pintype "bidirectional"))
    )
    (net (code "59") (name "BLUETH_RTS") (class "Default")
      (node (ref "U2") (pin "12") (pinfunction "PD6(AIN0)_12") (pintype "bidirectional"))
    )
    (net (code "60") (name "BLUETH_RXD") (class "Default")
      (node (ref "U2") (pin "11") (pinfunction "PD5(T1)_11") (pintype "bidirectional"))
    )
    (net (code "61") (name "BLUETH_TXD") (class "Default")
      (node (ref "U2") (pin "6") (pinfunction "PD4(XCK/T0)_6") (pintype "bidirectional"))
    )
    (net (code "62") (name "GND") (class "Default")
      (node (ref "12V") (pin "1") (pinfunction "1_1") (pintype "passive"))
      (node (ref "5V") (pin "1") (pinfunction "1_1") (pintype "passive"))
      (node (ref "C1") (pin "2") (pinfunction "2_2") (pintype "passive"))
      (node (ref "C10") (pin "2") (pinfunction "2_2") (pintype "passive"))
      (node (ref "C11") (pin "2") (pinfunction "2_2") (pintype "passive"))
      (node (ref "C12") (pin "2") (pinfunction "2_2") (pintype "passive"))
      (node (ref "C13") (pin "2") (pinfunction "2_2") (pintype "passive"))
      (node (ref "C14") (pin "2") (pinfunction "2_2") (pintype "passive"))
      (node (ref "C15") (pin "2") (pinfunction "2_2") (pintype "passive"))
      (node (ref "C16") (pin "2") (pinfunction "2_2") (pintype "passive"))
      (node (ref "C17") (pin "2") (pinfunction "2_2") (pintype "passive"))
      (node (ref "C18") (pin "2") (pinfunction "2_2") (pintype "passive"))
      (node (ref "C19") (pin "2") (pinfunction "2_2") (pintype "passive"))
      (node (ref "C2") (pin "2") (pinfunction "2_2") (pintype "passive"))
      (node (ref "C20") (pin "2") (pinfunction "2_2") (pintype "passive"))
      (node (ref "C21") (pin "2") (pinfunction "2_2") (pintype "passive"))
      (node (ref "C22") (pin "2") (pinfunction "2_2") (pintype "passive"))
      (node (ref "C23") (pin "2") (pinfunction "2_2") (pintype "passive"))
      (node (ref "C24") (pin "2") (pinfunction "2_2") (pintype "passive"))
      (node (ref "C25") (pin "2") (pinfunction "2_2") (pintype "passive"))
      (node (ref "C26") (pin "2") (pinfunction "2_2") (pintype "passive"))
      (node (ref "C27") (pin "2") (pinfunction "2_2") (pintype "passive"))
      (node (ref "C28") (pin "2") (pinfunction "2_2") (pintype "passive"))
      (node (ref "C29") (pin "2") (pinfunction "2_2") (pintype "passive"))
      (node (ref "C3") (pin "2") (pinfunction "2_2") (pintype "passive"))
      (node (ref "C30") (pin "2") (pinfunction "2_2") (pintype "passive"))
      (node (ref "C31") (pin "2") (pinfunction "2_2") (pintype "passive"))
      (node (ref "C32") (pin "2") (pinfunction "2_2") (pintype "passive"))
      (node (ref "C4") (pin "2") (pinfunction "2_2") (pintype "passive"))
      (node (ref "C5") (pin "2") (pinfunction "2_2") (pintype "passive"))
      (node (ref "C6") (pin "2") (pinfunction "2_2") (pintype "passive"))
      (node (ref "C7") (pin "2") (pinfunction "2_2") (pintype "passive"))
      (node (ref "C8") (pin "2") (pinfunction "2_2") (pintype "passive"))
      (node (ref "C9") (pin "2") (pinfunction "2_2") (pintype "passive"))
      (node (ref "D1") (pin "C") (pinfunction "C_C") (pintype "passive"))
      (node (ref "FAN1") (pin "1") (pinfunction "1_1") (pintype "passive"))
      (node (ref "FAN2") (pin "1") (pinfunction "1_1") (pintype "passive"))
      (node (ref "FAN3") (pin "1") (pinfunction "1_1") (pintype "passive"))
      (node (ref "FAN4") (pin "1") (pinfunction "1_1") (pintype "passive"))
      (node (ref "GPS") (pin "P$12") (pinfunction "GND_P$12") (pintype "bidirectional"))
      (node (ref "GPS") (pin "P$19") (pinfunction "GND_P$19") (pintype "bidirectional"))
      (node (ref "GPS") (pin "P$3") (pinfunction "GND_P$3") (pintype "bidirectional"))
      (node (ref "GPS") (pin "P$8") (pinfunction "GND_P$8") (pintype "bidirectional"))
      (node (ref "J1") (pin "P$1") (pinfunction "GND_P$1") (pintype "bidirectional"))
      (node (ref "J1") (pin "P$2") (pinfunction "GND_P$2") (pintype "bidirectional"))
      (node (ref "J2") (pin "6") (pinfunction "6_6") (pintype "passive"))
      (node (ref "LCD") (pin "1") (pinfunction "1_1") (pintype "passive"))
      (node (ref "LCD") (pin "16") (pinfunction "16_16") (pintype "passive"))
      (node (ref "LCD") (pin "5") (pinfunction "5_5") (pintype "passive"))
      (node (ref "R40") (pin "1") (pinfunction "1_1") (pintype "passive"))
      (node (ref "RS-485-1") (pin "GND") (pinfunction "GND_GND") (pintype "bidirectional"))
      (node (ref "RS-485-2") (pin "GND") (pinfunction "GND_GND") (pintype "bidirectional"))
      (node (ref "RS-485-3") (pin "GND") (pinfunction "GND_GND") (pintype "bidirectional"))
      (node (ref "RS-485-4") (pin "GND") (pinfunction "GND_GND") (pintype "bidirectional"))
      (node (ref "RS-485-5") (pin "GND") (pinfunction "GND_GND") (pintype "bidirectional"))
      (node (ref "RS-485-6") (pin "GND") (pinfunction "GND_GND") (pintype "bidirectional"))
      (node (ref "RS_TRANS_1") (pin "GND") (pinfunction "GND_GND") (pintype "bidirectional"))
      (node (ref "RS_TRANS_10") (pin "GND") (pinfunction "GND_GND") (pintype "bidirectional"))
      (node (ref "RS_TRANS_11") (pin "GND") (pinfunction "GND_GND") (pintype "bidirectional"))
      (node (ref "RS_TRANS_12") (pin "GND") (pinfunction "GND_GND") (pintype "bidirectional"))
      (node (ref "RS_TRANS_2") (pin "GND") (pinfunction "GND_GND") (pintype "bidirectional"))
      (node (ref "RS_TRANS_3") (pin "GND") (pinfunction "GND_GND") (pintype "bidirectional"))
      (node (ref "RS_TRANS_4") (pin "GND") (pinfunction "GND_GND") (pintype "bidirectional"))
      (node (ref "RS_TRANS_5") (pin "GND") (pinfunction "GND_GND") (pintype "bidirectional"))
      (node (ref "RS_TRANS_6") (pin "GND") (pinfunction "GND_GND") (pintype "bidirectional"))
      (node (ref "RS_TRANS_7") (pin "GND") (pinfunction "GND_GND") (pintype "bidirectional"))
      (node (ref "RS_TRANS_8") (pin "GND") (pinfunction "GND_GND") (pintype "bidirectional"))
      (node (ref "RS_TRANS_9") (pin "GND") (pinfunction "GND_GND") (pintype "bidirectional"))
      (node (ref "U$1") (pin "GND") (pinfunction "GND_GND") (pintype "bidirectional"))
      (node (ref "U$2") (pin "P$1") (pinfunction "E_P$1") (pintype "passive"))
      (node (ref "U$3") (pin "GND1") (pinfunction "GND1_GND1") (pintype "bidirectional"))
      (node (ref "U$3") (pin "GND2") (pinfunction "GND2_GND2") (pintype "power_in"))
      (node (ref "U1") (pin "11") (pinfunction "GND_11") (pintype "bidirectional"))
      (node (ref "U1") (pin "29") (pinfunction "GND_29") (pintype "bidirectional"))
      (node (ref "U1") (pin "30") (pinfunction "GND_30") (pintype "bidirectional"))
      (node (ref "U1") (pin "39") (pinfunction "GND_39") (pintype "bidirectional"))
      (node (ref "U1") (pin "40") (pinfunction "GND_40") (pintype "bidirectional"))
      (node (ref "U1_MUX") (pin "6") (pinfunction "~{E}_6") (pintype "input"))
      (node (ref "U1_MUX") (pin "7") (pinfunction "VEE_7") (pintype "power_in"))
      (node (ref "U1_MUX") (pin "8") (pinfunction "GND_8") (pintype "passive"))
      (node (ref "U2") (pin "22") (pinfunction "GND_22") (pintype "bidirectional"))
      (node (ref "U2") (pin "8") (pinfunction "GND_8") (pintype "bidirectional"))
      (node (ref "U2_MUX") (pin "6") (pinfunction "~{E}_6") (pintype "input"))
      (node (ref "U2_MUX") (pin "7") (pinfunction "VEE_7") (pintype "power_in"))
      (node (ref "U2_MUX") (pin "8") (pinfunction "GND_8") (pintype "passive"))
      (node (ref "U3_MUX") (pin "6") (pinfunction "~{E}_6") (pintype "input"))
      (node (ref "U3_MUX") (pin "7") (pinfunction "VEE_7") (pintype "power_in"))
      (node (ref "U3_MUX") (pin "8") (pinfunction "GND_8") (pintype "passive"))
      (node (ref "U4_MUX") (pin "6") (pinfunction "~{E}_6") (pintype "input"))
      (node (ref "U4_MUX") (pin "7") (pinfunction "VEE_7") (pintype "power_in"))
      (node (ref "U4_MUX") (pin "8") (pinfunction "GND_8") (pintype "passive"))
      (node (ref "U5_MUX") (pin "6") (pinfunction "~{E}_6") (pintype "input"))
      (node (ref "U5_MUX") (pin "7") (pinfunction "VEE_7") (pintype "power_in"))
      (node (ref "U5_MUX") (pin "8") (pinfunction "GND_8") (pintype "passive"))
      (node (ref "U7_MUX") (pin "6") (pinfunction "~{E}_6") (pintype "input"))
      (node (ref "U7_MUX") (pin "7") (pinfunction "VEE_7") (pintype "power_in"))
      (node (ref "U7_MUX") (pin "8") (pinfunction "GND_8") (pintype "passive"))
    )
    (net (code "63") (name "GPS_RX") (class "Default")
      (node (ref "D3") (pin "C") (pinfunction "C_C") (pintype "passive"))
      (node (ref "U2") (pin "4") (pinfunction "PD2(INT0)_4") (pintype "bidirectional"))
    )
    (net (code "64") (name "GPS_TX") (class "Default")
      (node (ref "GPS") (pin "P$9") (pinfunction "TX_P$9") (pintype "bidirectional"))
      (node (ref "U2") (pin "5") (pinfunction "PD3(INT1)_5") (pintype "bidirectional"))
    )
    (net (code "65") (name "LCD_D4") (class "Default")
      (node (ref "LCD") (pin "11") (pinfunction "11_11") (pintype "passive"))
      (node (ref "U$3") (pin "PF1") (pinfunction "PF1_PF1") (pintype "bidirectional"))
    )
    (net (code "66") (name "LCD_D5") (class "Default")
      (node (ref "LCD") (pin "12") (pinfunction "12_12") (pintype "passive"))
      (node (ref "U$3") (pin "PF2") (pinfunction "PF2_PF2") (pintype "bidirectional"))
    )
    (net (code "67") (name "LCD_D6") (class "Default")
      (node (ref "LCD") (pin "13") (pinfunction "13_13") (pintype "passive"))
      (node (ref "U$3") (pin "PF3") (pinfunction "PF3_PF3") (pintype "bidirectional"))
    )
    (net (code "68") (name "LCD_D7") (class "Default")
      (node (ref "LCD") (pin "14") (pinfunction "14_14") (pintype "passive"))
      (node (ref "U$3") (pin "PF4") (pinfunction "PF4_PF4") (pintype "bidirectional"))
    )
    (net (code "69") (name "LCD_EN") (class "Default")
      (node (ref "LCD") (pin "6") (pinfunction "6_6") (pintype "passive"))
      (node (ref "U$3") (pin "PF0") (pinfunction "PF0_PF0") (pintype "bidirectional"))
    )
    (net (code "70") (name "LCD_RS") (class "Default")
      (node (ref "LCD") (pin "4") (pinfunction "4_4") (pintype "passive"))
      (node (ref "U$3") (pin "PD3") (pinfunction "PD3_PD3") (pintype "bidirectional"))
    )
    (net (code "71") (name "Net-(D1-PadA)") (class "Default")
      (node (ref "D1") (pin "A") (pinfunction "A_A") (pintype "passive"))
      (node (ref "R1") (pin "2") (pinfunction "2_2") (pintype "passive"))
    )
    (net (code "72") (name "Net-(D2-PadC)") (class "Default")
      (node (ref "D2") (pin "C") (pinfunction "C_C") (pintype "passive"))
      (node (ref "R40") (pin "2") (pinfunction "2_2") (pintype "passive"))
    )
    (net (code "73") (name "Net-(GPS-3D-FIX)") (class "Default")
      (node (ref "D2") (pin "A") (pinfunction "A_A") (pintype "passive"))
      (node (ref "GPS") (pin "P$5") (pinfunction "3D-FIX_P$5") (pintype "bidirectional"))
    )
    (net (code "74") (name "Net-(GPS-EX_ANT)") (class "Default")
      (node (ref "GPS") (pin "P$11") (pinfunction "EX_ANT_P$11") (pintype "bidirectional"))
      (node (ref "J1") (pin "P$3") (pinfunction "SIGNAL_P$3") (pintype "bidirectional"))
    )
    (net (code "75") (name "Net-(GPS-RX)") (class "Default")
      (node (ref "D3") (pin "A") (pinfunction "A_A") (pintype "passive"))
      (node (ref "GPS") (pin "P$10") (pinfunction "RX_P$10") (pintype "bidirectional"))
      (node (ref "R41") (pin "1") (pinfunction "1_1") (pintype "passive"))
    )
    (net (code "76") (name "Net-(GPS-VCC)") (class "Default")
      (node (ref "C27") (pin "1") (pinfunction "1_1") (pintype "passive"))
      (node (ref "C28") (pin "1") (pinfunction "1_1") (pintype "passive"))
      (node (ref "GPS") (pin "P$1") (pinfunction "VCC_P$1") (pintype "bidirectional"))
      (node (ref "L1") (pin "2") (pinfunction "2_2") (pintype "passive"))
    )
    (net (code "77") (name "Net-(R26-Pad1)") (class "Default")
      (node (ref "R26") (pin "1") (pinfunction "1_1") (pintype "passive"))
      (node (ref "RS-485-1") (pin "A") (pinfunction "A_A") (pintype "bidirectional"))
      (node (ref "U$5") (pin "1") (pinfunction "1_1") (pintype "bidirectional"))
    )
    (net (code "78") (name "Net-(R26-Pad2)") (class "Default")
      (node (ref "R26") (pin "2") (pinfunction "2_2") (pintype "passive"))
      (node (ref "RS-485-1") (pin "B") (pinfunction "B_B") (pintype "bidirectional"))
      (node (ref "U$5") (pin "2") (pinfunction "2_2") (pintype "bidirectional"))
    )
    (net (code "79") (name "Net-(R27-Pad1)") (class "Default")
      (node (ref "R27") (pin "1") (pinfunction "1_1") (pintype "passive"))
      (node (ref "RS-485-2") (pin "A") (pinfunction "A_A") (pintype "bidirectional"))
      (node (ref "U$6") (pin "1") (pinfunction "1_1") (pintype "bidirectional"))
    )
    (net (code "80") (name "Net-(R27-Pad2)") (class "Default")
      (node (ref "R27") (pin "2") (pinfunction "2_2") (pintype "passive"))
      (node (ref "RS-485-2") (pin "B") (pinfunction "B_B") (pintype "bidirectional"))
      (node (ref "U$6") (pin "2") (pinfunction "2_2") (pintype "bidirectional"))
    )
    (net (code "81") (name "Net-(R28-Pad1)") (class "Default")
      (node (ref "R28") (pin "1") (pinfunction "1_1") (pintype "passive"))
      (node (ref "RS-485-1") (pin "Y") (pinfunction "Y_Y") (pintype "bidirectional"))
      (node (ref "U$5") (pin "3") (pinfunction "3_3") (pintype "bidirectional"))
    )
    (net (code "82") (name "Net-(R28-Pad2)") (class "Default")
      (node (ref "R28") (pin "2") (pinfunction "2_2") (pintype "passive"))
      (node (ref "RS-485-1") (pin "Z") (pinfunction "Z_Z") (pintype "bidirectional"))
      (node (ref "U$5") (pin "6") (pinfunction "6_6") (pintype "bidirectional"))
    )
    (net (code "83") (name "Net-(R29-Pad1)") (class "Default")
      (node (ref "R29") (pin "1") (pinfunction "1_1") (pintype "passive"))
      (node (ref "RS-485-2") (pin "Y") (pinfunction "Y_Y") (pintype "bidirectional"))
      (node (ref "U$6") (pin "3") (pinfunction "3_3") (pintype "bidirectional"))
    )
    (net (code "84") (name "Net-(R29-Pad2)") (class "Default")
      (node (ref "R29") (pin "2") (pinfunction "2_2") (pintype "passive"))
      (node (ref "RS-485-2") (pin "Z") (pinfunction "Z_Z") (pintype "bidirectional"))
      (node (ref "U$6") (pin "6") (pinfunction "6_6") (pintype "bidirectional"))
    )
    (net (code "85") (name "Net-(R30-Pad1)") (class "Default")
      (node (ref "R30") (pin "1") (pinfunction "1_1") (pintype "passive"))
      (node (ref "RS-485-3") (pin "A") (pinfunction "A_A") (pintype "bidirectional"))
      (node (ref "U$7") (pin "1") (pinfunction "1_1") (pintype "bidirectional"))
    )
    (net (code "86") (name "Net-(R30-Pad2)") (class "Default")
      (node (ref "R30") (pin "2") (pinfunction "2_2") (pintype "passive"))
      (node (ref "RS-485-3") (pin "B") (pinfunction "B_B") (pintype "bidirectional"))
      (node (ref "U$7") (pin "2") (pinfunction "2_2") (pintype "bidirectional"))
    )
    (net (code "87") (name "Net-(R31-Pad1)") (class "Default")
      (node (ref "R31") (pin "1") (pinfunction "1_1") (pintype "passive"))
      (node (ref "RS-485-4") (pin "A") (pinfunction "A_A") (pintype "bidirectional"))
      (node (ref "U$8") (pin "1") (pinfunction "1_1") (pintype "bidirectional"))
    )
    (net (code "88") (name "Net-(R31-Pad2)") (class "Default")
      (node (ref "R31") (pin "2") (pinfunction "2_2") (pintype "passive"))
      (node (ref "RS-485-4") (pin "B") (pinfunction "B_B") (pintype "bidirectional"))
      (node (ref "U$8") (pin "2") (pinfunction "2_2") (pintype "bidirectional"))
    )
    (net (code "89") (name "Net-(R32-Pad1)") (class "Default")
      (node (ref "R32") (pin "1") (pinfunction "1_1") (pintype "passive"))
      (node (ref "RS-485-3") (pin "Y") (pinfunction "Y_Y") (pintype "bidirectional"))
      (node (ref "U$7") (pin "3") (pinfunction "3_3") (pintype "bidirectional"))
    )
    (net (code "90") (name "Net-(R32-Pad2)") (class "Default")
      (node (ref "R32") (pin "2") (pinfunction "2_2") (pintype "passive"))
      (node (ref "RS-485-3") (pin "Z") (pinfunction "Z_Z") (pintype "bidirectional"))
      (node (ref "U$7") (pin "6") (pinfunction "6_6") (pintype "bidirectional"))
    )
    (net (code "91") (name "Net-(R33-Pad1)") (class "Default")
      (node (ref "R33") (pin "1") (pinfunction "1_1") (pintype "passive"))
      (node (ref "RS-485-4") (pin "Y") (pinfunction "Y_Y") (pintype "bidirectional"))
      (node (ref "U$8") (pin "3") (pinfunction "3_3") (pintype "bidirectional"))
    )
    (net (code "92") (name "Net-(R33-Pad2)") (class "Default")
      (node (ref "R33") (pin "2") (pinfunction "2_2") (pintype "passive"))
      (node (ref "RS-485-4") (pin "Z") (pinfunction "Z_Z") (pintype "bidirectional"))
      (node (ref "U$8") (pin "6") (pinfunction "6_6") (pintype "bidirectional"))
    )
    (net (code "93") (name "Net-(R34-Pad1)") (class "Default")
      (node (ref "R34") (pin "1") (pinfunction "1_1") (pintype "passive"))
      (node (ref "RS-485-5") (pin "A") (pinfunction "A_A") (pintype "bidirectional"))
      (node (ref "U$9") (pin "1") (pinfunction "1_1") (pintype "bidirectional"))
    )
    (net (code "94") (name "Net-(R34-Pad2)") (class "Default")
      (node (ref "R34") (pin "2") (pinfunction "2_2") (pintype "passive"))
      (node (ref "RS-485-5") (pin "B") (pinfunction "B_B") (pintype "bidirectional"))
      (node (ref "U$9") (pin "2") (pinfunction "2_2") (pintype "bidirectional"))
    )
    (net (code "95") (name "Net-(R35-Pad1)") (class "Default")
      (node (ref "R35") (pin "1") (pinfunction "1_1") (pintype "passive"))
      (node (ref "RS-485-5") (pin "Y") (pinfunction "Y_Y") (pintype "bidirectional"))
      (node (ref "U$9") (pin "3") (pinfunction "3_3") (pintype "bidirectional"))
    )
    (net (code "96") (name "Net-(R35-Pad2)") (class "Default")
      (node (ref "R35") (pin "2") (pinfunction "2_2") (pintype "passive"))
      (node (ref "RS-485-5") (pin "Z") (pinfunction "Z_Z") (pintype "bidirectional"))
      (node (ref "U$9") (pin "6") (pinfunction "6_6") (pintype "bidirectional"))
    )
    (net (code "97") (name "Net-(R36-Pad1)") (class "Default")
      (node (ref "R36") (pin "1") (pinfunction "1_1") (pintype "passive"))
      (node (ref "RS-485-6") (pin "A") (pinfunction "A_A") (pintype "bidirectional"))
      (node (ref "U$10") (pin "1") (pinfunction "1_1") (pintype "bidirectional"))
    )
    (net (code "98") (name "Net-(R36-Pad2)") (class "Default")
      (node (ref "R36") (pin "2") (pinfunction "2_2") (pintype "passive"))
      (node (ref "RS-485-6") (pin "B") (pinfunction "B_B") (pintype "bidirectional"))
      (node (ref "U$10") (pin "2") (pinfunction "2_2") (pintype "bidirectional"))
    )
    (net (code "99") (name "Net-(R37-Pad1)") (class "Default")
      (node (ref "R37") (pin "1") (pinfunction "1_1") (pintype "passive"))
      (node (ref "RS-485-6") (pin "Y") (pinfunction "Y_Y") (pintype "bidirectional"))
      (node (ref "U$10") (pin "3") (pinfunction "3_3") (pintype "bidirectional"))
    )
    (net (code "100") (name "Net-(R37-Pad2)") (class "Default")
      (node (ref "R37") (pin "2") (pinfunction "2_2") (pintype "passive"))
      (node (ref "RS-485-6") (pin "Z") (pinfunction "Z_Z") (pintype "bidirectional"))
      (node (ref "U$10") (pin "6") (pinfunction "6_6") (pintype "bidirectional"))
    )
    (net (code "101") (name "Net-(U$2-S)") (class "Default")
      (node (ref "LCD") (pin "3") (pinfunction "3_3") (pintype "passive"))
      (node (ref "U$2") (pin "P$2") (pinfunction "S_P$2") (pintype "passive"))
    )
    (net (code "102") (name "Net-(U2-PB6(XTAL1{slash}TOSC1))") (class "Default")
      (node (ref "C31") (pin "1") (pinfunction "1_1") (pintype "passive"))
      (node (ref "U2") (pin "9") (pinfunction "PB6(XTAL1/TOSC1)_9") (pintype "bidirectional"))
      (node (ref "Y1") (pin "2") (pinfunction "2_2") (pintype "passive"))
    )
    (net (code "103") (name "Net-(U2-PB7(XTAL2{slash}TOSC2))") (class "Default")
      (node (ref "C32") (pin "1") (pinfunction "1_1") (pintype "passive"))
      (node (ref "U2") (pin "10") (pinfunction "PB7(XTAL2/TOSC2)_10") (pintype "bidirectional"))
      (node (ref "Y1") (pin "1") (pinfunction "1_1") (pintype "passive"))
    )
    (net (code "104") (name "RESET") (class "Default")
      (node (ref "J2") (pin "5") (pinfunction "5_5") (pintype "passive"))
      (node (ref "R39") (pin "1") (pinfunction "1_1") (pintype "passive"))
      (node (ref "U$3") (pin "RST") (pinfunction "RST_RST") (pintype "power_in"))
      (node (ref "U1") (pin "22") (pinfunction "/RESET_22") (pintype "bidirectional"))
      (node (ref "U2") (pin "1") (pinfunction "PC6(/RESET)_1") (pintype "bidirectional"))
    )
    (net (code "105") (name "RS485_1_RX") (class "Default")
      (node (ref "RS_TRANS_1") (pin "RO") (pinfunction "R0_RO") (pintype "bidirectional"))
      (node (ref "U1_MUX") (pin "12") (pinfunction "1Y0_12") (pintype "bidirectional"))
    )
    (net (code "106") (name "RS485_1_TX") (class "Default")
      (node (ref "RS_TRANS_1") (pin "DI") (pinfunction "DI_DI") (pintype "bidirectional"))
      (node (ref "U1_MUX") (pin "1") (pinfunction "2Y0_1") (pintype "bidirectional"))
    )
    (net (code "107") (name "RS485_2_RX") (class "Default")
      (node (ref "RS_TRANS_3") (pin "RO") (pinfunction "R0_RO") (pintype "bidirectional"))
      (node (ref "U2_MUX") (pin "12") (pinfunction "1Y0_12") (pintype "bidirectional"))
    )
    (net (code "108") (name "RS485_2_TX") (class "Default")
      (node (ref "RS_TRANS_3") (pin "DI") (pinfunction "DI_DI") (pintype "bidirectional"))
      (node (ref "U2_MUX") (pin "1") (pinfunction "2Y0_1") (pintype "bidirectional"))
    )
    (net (code "109") (name "RS485_3_RX") (class "Default")
      (node (ref "RS_TRANS_5") (pin "RO") (pinfunction "R0_RO") (pintype "bidirectional"))
      (node (ref "U3_MUX") (pin "12") (pinfunction "1Y0_12") (pintype "bidirectional"))
    )
    (net (code "110") (name "RS485_3_TX") (class "Default")
      (node (ref "RS_TRANS_5") (pin "DI") (pinfunction "DI_DI") (pintype "bidirectional"))
      (node (ref "U3_MUX") (pin "1") (pinfunction "2Y0_1") (pintype "bidirectional"))
    )
    (net (code "111") (name "RS485_4_RX") (class "Default")
      (node (ref "RS_TRANS_7") (pin "RO") (pinfunction "R0_RO") (pintype "bidirectional"))
      (node (ref "U4_MUX") (pin "12") (pinfunction "1Y0_12") (pintype "bidirectional"))
    )
    (net (code "112") (name "RS485_4_TX") (class "Default")
      (node (ref "RS_TRANS_7") (pin "DI") (pinfunction "DI_DI") (pintype "bidirectional"))
      (node (ref "U4_MUX") (pin "1") (pinfunction "2Y0_1") (pintype "bidirectional"))
    )
    (net (code "113") (name "RS485_5_RX") (class "Default")
      (node (ref "RS_TRANS_9") (pin "RO") (pinfunction "R0_RO") (pintype "bidirectional"))
      (node (ref "U4_MUX") (pin "14") (pinfunction "1Y1_14") (pintype "bidirectional"))
    )
    (net (code "114") (name "RS485_5_TX") (class "Default")
      (node (ref "RS_TRANS_9") (pin "DI") (pinfunction "DI_DI") (pintype "bidirectional"))
      (node (ref "U4_MUX") (pin "5") (pinfunction "2Y1_5") (pintype "bidirectional"))
    )
    (net (code "115") (name "RS485_6_RX") (class "Default")
      (node (ref "RS_TRANS_11") (pin "RO") (pinfunction "R0_RO") (pintype "bidirectional"))
      (node (ref "U3_MUX") (pin "14") (pinfunction "1Y1_14") (pintype "bidirectional"))
    )
    (net (code "116") (name "RS485_6_TX") (class "Default")
      (node (ref "RS_TRANS_11") (pin "DI") (pinfunction "DI_DI") (pintype "bidirectional"))
      (node (ref "U3_MUX") (pin "5") (pinfunction "2Y1_5") (pintype "bidirectional"))
    )
    (net (code "117") (name "RS485_7_RX") (class "Default")
      (node (ref "RS_TRANS_2") (pin "RO") (pinfunction "R0_RO") (pintype "bidirectional"))
      (node (ref "U2_MUX") (pin "14") (pinfunction "1Y1_14") (pintype "bidirectional"))
    )
    (net (code "118") (name "RS485_7_TX") (class "Default")
      (node (ref "RS_TRANS_2") (pin "DI") (pinfunction "DI_DI") (pintype "bidirectional"))
      (node (ref "U2_MUX") (pin "5") (pinfunction "2Y1_5") (pintype "bidirectional"))
    )
    (net (code "119") (name "RS485_8_RX") (class "Default")
      (node (ref "RS_TRANS_4") (pin "RO") (pinfunction "R0_RO") (pintype "bidirectional"))
      (node (ref "U1_MUX") (pin "14") (pinfunction "1Y1_14") (pintype "bidirectional"))
    )
    (net (code "120") (name "RS485_8_TX") (class "Default")
      (node (ref "RS_TRANS_4") (pin "DI") (pinfunction "DI_DI") (pintype "bidirectional"))
      (node (ref "U1_MUX") (pin "5") (pinfunction "2Y1_5") (pintype "bidirectional"))
    )
    (net (code "121") (name "RS485_9_RX") (class "Default")
      (node (ref "RS_TRANS_6") (pin "RO") (pinfunction "R0_RO") (pintype "bidirectional"))
      (node (ref "U1_MUX") (pin "15") (pinfunction "1Y2_15") (pintype "bidirectional"))
    )
    (net (code "122") (name "RS485_9_TX") (class "Default")
      (node (ref "RS_TRANS_6") (pin "DI") (pinfunction "DI_DI") (pintype "bidirectional"))
      (node (ref "U1_MUX") (pin "2") (pinfunction "2Y2_2") (pintype "bidirectional"))
    )
    (net (code "123") (name "RS485_10_RX") (class "Default")
      (node (ref "RS_TRANS_8") (pin "RO") (pinfunction "R0_RO") (pintype "bidirectional"))
      (node (ref "U2_MUX") (pin "15") (pinfunction "1Y2_15") (pintype "bidirectional"))
    )
    (net (code "124") (name "RS485_10_TX") (class "Default")
      (node (ref "RS_TRANS_8") (pin "DI") (pinfunction "DI_DI") (pintype "bidirectional"))
      (node (ref "U2_MUX") (pin "2") (pinfunction "2Y2_2") (pintype "bidirectional"))
    )
    (net (code "125") (name "RS485_11_RX") (class "Default")
      (node (ref "RS_TRANS_10") (pin "RO") (pinfunction "R0_RO") (pintype "bidirectional"))
      (node (ref "U3_MUX") (pin "15") (pinfunction "1Y2_15") (pintype "bidirectional"))
    )
    (net (code "126") (name "RS485_11_TX") (class "Default")
      (node (ref "RS_TRANS_10") (pin "DI") (pinfunction "DI_DI") (pintype "bidirectional"))
      (node (ref "U3_MUX") (pin "2") (pinfunction "2Y2_2") (pintype "bidirectional"))
    )
    (net (code "127") (name "RS485_12_RX") (class "Default")
      (node (ref "RS_TRANS_12") (pin "RO") (pinfunction "R0_RO") (pintype "bidirectional"))
      (node (ref "U4_MUX") (pin "15") (pinfunction "1Y2_15") (pintype "bidirectional"))
    )
    (net (code "128") (name "RS485_12_TX") (class "Default")
      (node (ref "RS_TRANS_12") (pin "DI") (pinfunction "DI_DI") (pintype "bidirectional"))
      (node (ref "U4_MUX") (pin "2") (pinfunction "2Y2_2") (pintype "bidirectional"))
    )
    (net (code "129") (name "RS485_13_RX") (class "Default")
      (node (ref "RS-485-1") (pin "RO") (pinfunction "R0_RO") (pintype "bidirectional"))
      (node (ref "U5_MUX") (pin "12") (pinfunction "1Y0_12") (pintype "bidirectional"))
    )
    (net (code "130") (name "RS485_13_TX") (class "Default")
      (node (ref "RS-485-1") (pin "DI") (pinfunction "DI_DI") (pintype "bidirectional"))
      (node (ref "U5_MUX") (pin "1") (pinfunction "2Y0_1") (pintype "bidirectional"))
    )
    (net (code "131") (name "RS485_14_RX") (class "Default")
      (node (ref "RS-485-3") (pin "RO") (pinfunction "R0_RO") (pintype "bidirectional"))
      (node (ref "U5_MUX") (pin "14") (pinfunction "1Y1_14") (pintype "bidirectional"))
    )
    (net (code "132") (name "RS485_14_TX") (class "Default")
      (node (ref "RS-485-3") (pin "DI") (pinfunction "DI_DI") (pintype "bidirectional"))
      (node (ref "U5_MUX") (pin "5") (pinfunction "2Y1_5") (pintype "bidirectional"))
    )
    (net (code "133") (name "RS485_15_RX") (class "Default")
      (node (ref "RS-485-5") (pin "RO") (pinfunction "R0_RO") (pintype "bidirectional"))
      (node (ref "U5_MUX") (pin "15") (pinfunction "1Y2_15") (pintype "bidirectional"))
    )
    (net (code "134") (name "RS485_15_TX") (class "Default")
      (node (ref "RS-485-5") (pin "DI") (pinfunction "DI_DI") (pintype "bidirectional"))
      (node (ref "U5_MUX") (pin "2") (pinfunction "2Y2_2") (pintype "bidirectional"))
    )
    (net (code "135") (name "RS485_16_RX") (class "Default")
      (node (ref "RS-485-6") (pin "RO") (pinfunction "R0_RO") (pintype "bidirectional"))
      (node (ref "U7_MUX") (pin "12") (pinfunction "1Y0_12") (pintype "bidirectional"))
    )
    (net (code "136") (name "RS485_16_TX") (class "Default")
      (node (ref "RS-485-6") (pin "DI") (pinfunction "DI_DI") (pintype "bidirectional"))
      (node (ref "U7_MUX") (pin "1") (pinfunction "2Y0_1") (pintype "bidirectional"))
    )
    (net (code "137") (name "RS485_17_RX") (class "Default")
      (node (ref "RS-485-2") (pin "RO") (pinfunction "R0_RO") (pintype "bidirectional"))
      (node (ref "U7_MUX") (pin "14") (pinfunction "1Y1_14") (pintype "bidirectional"))
    )
    (net (code "138") (name "RS485_17_TX") (class "Default")
      (node (ref "RS-485-2") (pin "DI") (pinfunction "DI_DI") (pintype "bidirectional"))
      (node (ref "U7_MUX") (pin "5") (pinfunction "2Y1_5") (pintype "bidirectional"))
    )
    (net (code "139") (name "RS485_18_RX") (class "Default")
      (node (ref "RS-485-4") (pin "RO") (pinfunction "R0_RO") (pintype "bidirectional"))
      (node (ref "U7_MUX") (pin "15") (pinfunction "1Y2_15") (pintype "bidirectional"))
    )
    (net (code "140") (name "RS485_18_TX") (class "Default")
      (node (ref "RS-485-4") (pin "DI") (pinfunction "DI_DI") (pintype "bidirectional"))
      (node (ref "U7_MUX") (pin "2") (pinfunction "2Y2_2") (pintype "bidirectional"))
    )
    (net (code "141") (name "TCP_INT") (class "Default")
      (node (ref "U$3") (pin "PD2") (pinfunction "PD2_PD2") (pintype "bidirectional"))
      (node (ref "U1") (pin "28") (pinfunction "/INT_28") (pintype "bidirectional"))
    )
    (net (code "142") (name "TCP_MISO") (class "Default")
      (node (ref "U$3") (pin "PA4") (pinfunction "PA4_PA4") (pintype "bidirectional"))
      (node (ref "U1") (pin "2") (pinfunction "MISO_2") (pintype "bidirectional"))
    )
    (net (code "143") (name "TCP_MOSI") (class "Default")
      (node (ref "U$3") (pin "PA5") (pinfunction "PA5_PA5") (pintype "bidirectional"))
      (node (ref "U1") (pin "1") (pinfunction "MOSI_1") (pintype "bidirectional"))
    )
    (net (code "144") (name "TCP_SCLK") (class "Default")
      (node (ref "U$3") (pin "PA2") (pinfunction "PA2_PA2") (pintype "bidirectional"))
      (node (ref "U1") (pin "23") (pinfunction "SCLK_23") (pintype "bidirectional"))
    )
    (net (code "145") (name "TCP_SS") (class "Default")
      (node (ref "U$3") (pin "PA3") (pinfunction "PA3_PA3") (pintype "bidirectional"))
      (node (ref "U1") (pin "24") (pinfunction "/SCS_24") (pintype "bidirectional"))
    )
    (net (code "146") (name "TEMP") (class "Default")
      (node (ref "U2") (pin "23") (pinfunction "PC0(ADC0)_23") (pintype "bidirectional"))
    )
    (net (code "147") (name "U1RX") (class "Default")
      (node (ref "U$3") (pin "PB0") (pinfunction "PB0_PB0") (pintype "bidirectional"))
      (node (ref "U1_MUX") (pin "13") (pinfunction "1Z_13") (pintype "bidirectional"))
    )
    (net (code "148") (name "U1TX") (class "Default")
      (node (ref "U$3") (pin "PB1") (pinfunction "PB1_PB1") (pintype "bidirectional"))
      (node (ref "U1_MUX") (pin "3") (pinfunction "2Z_3") (pintype "bidirectional"))
    )
    (net (code "149") (name "U1_MUX_S0") (class "Default")
      (node (ref "U$3") (pin "PA6") (pinfunction "PA6_PA6") (pintype "bidirectional"))
      (node (ref "U1_MUX") (pin "10") (pinfunction "S0_10") (pintype "input"))
    )
    (net (code "150") (name "U1_MUX_S1") (class "Default")
      (node (ref "U$3") (pin "PA7") (pinfunction "PA7_PA7") (pintype "bidirectional"))
      (node (ref "U1_MUX") (pin "9") (pinfunction "S1_9") (pintype "input"))
    )
    (net (code "151") (name "U2RX") (class "Default")
      (node (ref "U$3") (pin "PD6") (pinfunction "PD6_PD6") (pintype "bidirectional"))
      (node (ref "U2_MUX") (pin "13") (pinfunction "1Z_13") (pintype "bidirectional"))
    )
    (net (code "152") (name "U2TX") (class "Default")
      (node (ref "U$3") (pin "PD7") (pinfunction "PD7_PD7") (pintype "bidirectional"))
      (node (ref "U2_MUX") (pin "3") (pinfunction "2Z_3") (pintype "bidirectional"))
    )
    (net (code "153") (name "U2_MUX_S0") (class "Default")
      (node (ref "U$3") (pin "PE2") (pinfunction "PE2_PE2") (pintype "bidirectional"))
      (node (ref "U2_MUX") (pin "10") (pinfunction "S0_10") (pintype "input"))
    )
    (net (code "154") (name "U2_MUX_S1") (class "Default")
      (node (ref "U$3") (pin "PE3") (pinfunction "PE3_PE3") (pintype "bidirectional"))
      (node (ref "U2_MUX") (pin "9") (pinfunction "S1_9") (pintype "input"))
    )
    (net (code "155") (name "U3RX") (class "Default")
      (node (ref "U$3") (pin "PC6") (pinfunction "PC6_PC6") (pintype "bidirectional"))
      (node (ref "U3_MUX") (pin "13") (pinfunction "1Z_13") (pintype "bidirectional"))
    )
    (net (code "156") (name "U3TX") (class "Default")
      (node (ref "U$3") (pin "PC7") (pinfunction "PC7_PC7") (pintype "bidirectional"))
      (node (ref "U3_MUX") (pin "3") (pinfunction "2Z_3") (pintype "bidirectional"))
    )
    (net (code "157") (name "U3_MUX_S0") (class "Default")
      (node (ref "U$3") (pin "PB2") (pinfunction "PB2_PB2") (pintype "bidirectional"))
      (node (ref "U3_MUX") (pin "10") (pinfunction "S0_10") (pintype "input"))
    )
    (net (code "158") (name "U3_MUX_S1") (class "Default")
      (node (ref "U$3") (pin "PB3") (pinfunction "PB3_PB3") (pintype "bidirectional"))
      (node (ref "U3_MUX") (pin "9") (pinfunction "S1_9") (pintype "input"))
    )
    (net (code "159") (name "U4RX") (class "Default")
      (node (ref "U$3") (pin "PC4") (pinfunction "PC4_PC4") (pintype "bidirectional"))
      (node (ref "U4_MUX") (pin "13") (pinfunction "1Z_13") (pintype "bidirectional"))
    )
    (net (code "160") (name "U4TX") (class "Default")
      (node (ref "U$3") (pin "PC5") (pinfunction "PC5_PC5") (pintype "bidirectional"))
      (node (ref "U4_MUX") (pin "3") (pinfunction "2Z_3") (pintype "bidirectional"))
    )
    (net (code "161") (name "U4_MUX_S0") (class "Default")
      (node (ref "U$3") (pin "PB4") (pinfunction "PB4_PB4") (pintype "bidirectional"))
      (node (ref "U4_MUX") (pin "10") (pinfunction "S0_10") (pintype "input"))
    )
    (net (code "162") (name "U4_MUX_S1") (class "Default")
      (node (ref "U$3") (pin "PB5") (pinfunction "PB5_PB5") (pintype "bidirectional"))
      (node (ref "U4_MUX") (pin "9") (pinfunction "S1_9") (pintype "input"))
    )
    (net (code "163") (name "U5RX") (class "Default")
      (node (ref "U$3") (pin "PE4") (pinfunction "PE4_PE4") (pintype "bidirectional"))
      (node (ref "U5_MUX") (pin "13") (pinfunction "1Z_13") (pintype "bidirectional"))
    )
    (net (code "164") (name "U5TX") (class "Default")
      (node (ref "U$3") (pin "PE5") (pinfunction "PE5_PE5") (pintype "bidirectional"))
      (node (ref "U5_MUX") (pin "3") (pinfunction "2Z_3") (pintype "bidirectional"))
    )
    (net (code "165") (name "U5_MUX_S0") (class "Default")
      (node (ref "U$3") (pin "PB6") (pinfunction "PB6_PB6") (pintype "bidirectional"))
      (node (ref "U5_MUX") (pin "10") (pinfunction "S0_10") (pintype "input"))
    )
    (net (code "166") (name "U5_MUX_S1") (class "Default")
      (node (ref "U$3") (pin "PB7") (pinfunction "PB7_PB7") (pintype "bidirectional"))
      (node (ref "U5_MUX") (pin "9") (pinfunction "S1_9") (pintype "input"))
    )
    (net (code "167") (name "U7RX") (class "Default")
      (node (ref "U$3") (pin "PE0") (pinfunction "PE0_PE0") (pintype "bidirectional"))
      (node (ref "U7_MUX") (pin "13") (pinfunction "1Z_13") (pintype "bidirectional"))
    )
    (net (code "168") (name "U7TX") (class "Default")
      (node (ref "U$3") (pin "PE1") (pinfunction "PE1_PE1") (pintype "bidirectional"))
      (node (ref "U7_MUX") (pin "3") (pinfunction "2Z_3") (pintype "bidirectional"))
    )
    (net (code "169") (name "U7_MUX_S0") (class "Default")
      (node (ref "U$3") (pin "PD0") (pinfunction "PD0_PD0") (pintype "bidirectional"))
      (node (ref "U7_MUX") (pin "10") (pinfunction "S0_10") (pintype "input"))
    )
    (net (code "170") (name "U7_MUX_S1") (class "Default")
      (node (ref "U$3") (pin "PD1") (pinfunction "PD1_PD1") (pintype "bidirectional"))
      (node (ref "U7_MUX") (pin "9") (pinfunction "S1_9") (pintype "input"))
    )
    (net (code "171") (name "VBUS") (class "Default")
      (node (ref "U$3") (pin "VBUS") (pinfunction "VBUS_VBUS") (pintype "power_in"))
    )
    (net (code "172") (name "unconnected-(FAN1-Pad3)") (class "Default")
      (node (ref "FAN1") (pin "3") (pinfunction "3_3") (pintype "passive"))
    )
    (net (code "173") (name "unconnected-(FAN1-Pad4)") (class "Default")
      (node (ref "FAN1") (pin "4") (pinfunction "4_4") (pintype "passive"))
    )
    (net (code "174") (name "unconnected-(FAN2-Pad3)") (class "Default")
      (node (ref "FAN2") (pin "3") (pinfunction "3_3") (pintype "passive"))
    )
    (net (code "175") (name "unconnected-(FAN2-Pad4)") (class "Default")
      (node (ref "FAN2") (pin "4") (pinfunction "4_4") (pintype "passive"))
    )
    (net (code "176") (name "unconnected-(FAN3-Pad3)") (class "Default")
      (node (ref "FAN3") (pin "3") (pinfunction "3_3") (pintype "passive"))
    )
    (net (code "177") (name "unconnected-(FAN3-Pad4)") (class "Default")
      (node (ref "FAN3") (pin "4") (pinfunction "4_4") (pintype "passive"))
    )
    (net (code "178") (name "unconnected-(FAN4-Pad3)") (class "Default")
      (node (ref "FAN4") (pin "3") (pinfunction "3_3") (pintype "passive"))
    )
    (net (code "179") (name "unconnected-(FAN4-Pad4)") (class "Default")
      (node (ref "FAN4") (pin "4") (pinfunction "4_4") (pintype "passive"))
    )
    (net (code "180") (name "unconnected-(GPS-1PPS-PadP$13)") (class "Default")
      (node (ref "GPS") (pin "P$13") (pinfunction "1PPS_P$13") (pintype "bidirectional"))
    )
    (net (code "181") (name "unconnected-(GPS-NC-PadP$6)") (class "Default")
      (node (ref "GPS") (pin "P$6") (pinfunction "NC_P$6") (pintype "bidirectional"))
    )
    (net (code "182") (name "unconnected-(GPS-NC-PadP$7)") (class "Default")
      (node (ref "GPS") (pin "P$7") (pinfunction "NC_P$7") (pintype "bidirectional"))
    )
    (net (code "183") (name "unconnected-(GPS-NC-PadP$15)") (class "Default")
      (node (ref "GPS") (pin "P$15") (pinfunction "NC_P$15") (pintype "bidirectional"))
    )
    (net (code "184") (name "unconnected-(GPS-NC-PadP$16)") (class "Default")
      (node (ref "GPS") (pin "P$16") (pinfunction "NC_P$16") (pintype "bidirectional"))
    )
    (net (code "185") (name "unconnected-(GPS-NC-PadP$17)") (class "Default")
      (node (ref "GPS") (pin "P$17") (pinfunction "NC_P$17") (pintype "bidirectional"))
    )
    (net (code "186") (name "unconnected-(GPS-NC-PadP$18)") (class "Default")
      (node (ref "GPS") (pin "P$18") (pinfunction "NC_P$18") (pintype "bidirectional"))
    )
    (net (code "187") (name "unconnected-(GPS-NC-PadP$20)") (class "Default")
      (node (ref "GPS") (pin "P$20") (pinfunction "NC_P$20") (pintype "bidirectional"))
    )
    (net (code "188") (name "unconnected-(GPS-NRESET-PadP$2)") (class "Default")
      (node (ref "GPS") (pin "P$2") (pinfunction "NRESET_P$2") (pintype "bidirectional"))
    )
    (net (code "189") (name "unconnected-(GPS-RTCM-PadP$14)") (class "Default")
      (node (ref "GPS") (pin "P$14") (pinfunction "RTCM_P$14") (pintype "bidirectional"))
    )
    (net (code "190") (name "unconnected-(GPS-VBACKUP-PadP$4)") (class "Default")
      (node (ref "GPS") (pin "P$4") (pinfunction "VBACKUP_P$4") (pintype "bidirectional"))
    )
    (net (code "191") (name "unconnected-(H1-Pad1)") (class "Default")
      (node (ref "H1") (pin "1") (pinfunction "1_1") (pintype "passive"))
    )
    (net (code "192") (name "unconnected-(H2-Pad1)") (class "Default")
      (node (ref "H2") (pin "1") (pinfunction "1_1") (pintype "passive"))
    )
    (net (code "193") (name "unconnected-(H3-Pad1)") (class "Default")
      (node (ref "H3") (pin "1") (pinfunction "1_1") (pintype "passive"))
    )
    (net (code "194") (name "unconnected-(H4-Pad1)") (class "Default")
      (node (ref "H4") (pin "1") (pinfunction "1_1") (pintype "passive"))
    )
    (net (code "195") (name "unconnected-(LCD-Pad7)") (class "Default")
      (node (ref "LCD") (pin "7") (pinfunction "7_7") (pintype "passive"))
    )
    (net (code "196") (name "unconnected-(LCD-Pad8)") (class "Default")
      (node (ref "LCD") (pin "8") (pinfunction "8_8") (pintype "passive"))
    )
    (net (code "197") (name "unconnected-(LCD-Pad9)") (class "Default")
      (node (ref "LCD") (pin "9") (pinfunction "9_9") (pintype "passive"))
    )
    (net (code "198") (name "unconnected-(LCD-Pad10)") (class "Default")
      (node (ref "LCD") (pin "10") (pinfunction "10_10") (pintype "passive"))
    )
    (net (code "199") (name "unconnected-(U$4-Pad49)") (class "Default")
      (node (ref "U$4") (pin "49") (pinfunction "49_49") (pintype "bidirectional"))
    )
    (net (code "200") (name "unconnected-(U$4-Pad50)") (class "Default")
      (node (ref "U$4") (pin "50") (pinfunction "50_50") (pintype "bidirectional"))
    )
    (net (code "201") (name "unconnected-(U$4-Pad51)") (class "Default")
      (node (ref "U$4") (pin "51") (pinfunction "51_51") (pintype "bidirectional"))
    )
    (net (code "202") (name "unconnected-(U$4-Pad52)") (class "Default")
      (node (ref "U$4") (pin "52") (pinfunction "52_52") (pintype "bidirectional"))
    )
    (net (code "203") (name "unconnected-(U$4-Pad53)") (class "Default")
      (node (ref "U$4") (pin "53") (pinfunction "53_53") (pintype "bidirectional"))
    )
    (net (code "204") (name "unconnected-(U$4-Pad54)") (class "Default")
      (node (ref "U$4") (pin "54") (pinfunction "54_54") (pintype "bidirectional"))
    )
    (net (code "205") (name "unconnected-(U$4-Pad55)") (class "Default")
      (node (ref "U$4") (pin "55") (pinfunction "55_55") (pintype "bidirectional"))
    )
    (net (code "206") (name "unconnected-(U$4-Pad56)") (class "Default")
      (node (ref "U$4") (pin "56") (pinfunction "56_56") (pintype "bidirectional"))
    )
    (net (code "207") (name "unconnected-(U$4-Pad57)") (class "Default")
      (node (ref "U$4") (pin "57") (pinfunction "57_57") (pintype "bidirectional"))
    )
    (net (code "208") (name "unconnected-(U$4-Pad58)") (class "Default")
      (node (ref "U$4") (pin "58") (pinfunction "58_58") (pintype "bidirectional"))
    )
    (net (code "209") (name "unconnected-(U$4-Pad59)") (class "Default")
      (node (ref "U$4") (pin "59") (pinfunction "59_59") (pintype "bidirectional"))
    )
    (net (code "210") (name "unconnected-(U$4-Pad60)") (class "Default")
      (node (ref "U$4") (pin "60") (pinfunction "60_60") (pintype "bidirectional"))
    )
    (net (code "211") (name "unconnected-(U$4-Pad61)") (class "Default")
      (node (ref "U$4") (pin "61") (pinfunction "61_61") (pintype "bidirectional"))
    )
    (net (code "212") (name "unconnected-(U$4-Pad62)") (class "Default")
      (node (ref "U$4") (pin "62") (pinfunction "62_62") (pintype "bidirectional"))
    )
    (net (code "213") (name "unconnected-(U$4-Pad63)") (class "Default")
      (node (ref "U$4") (pin "63") (pinfunction "63_63") (pintype "bidirectional"))
    )
    (net (code "214") (name "unconnected-(U$4-Pad64)") (class "Default")
      (node (ref "U$4") (pin "64") (pinfunction "64_64") (pintype "bidirectional"))
    )
    (net (code "215") (name "unconnected-(U$4-Pad65)") (class "Default")
      (node (ref "U$4") (pin "65") (pinfunction "65_65") (pintype "bidirectional"))
    )
    (net (code "216") (name "unconnected-(U$4-Pad66)") (class "Default")
      (node (ref "U$4") (pin "66") (pinfunction "66_66") (pintype "bidirectional"))
    )
    (net (code "217") (name "unconnected-(U$4-Pad67)") (class "Default")
      (node (ref "U$4") (pin "67") (pinfunction "67_67") (pintype "bidirectional"))
    )
    (net (code "218") (name "unconnected-(U$4-Pad68)") (class "Default")
      (node (ref "U$4") (pin "68") (pinfunction "68_68") (pintype "bidirectional"))
    )
    (net (code "219") (name "unconnected-(U$5-Pad4)") (class "Default")
      (node (ref "U$5") (pin "4") (pinfunction "4_4") (pintype "bidirectional"))
    )
    (net (code "220") (name "unconnected-(U$5-Pad5)") (class "Default")
      (node (ref "U$5") (pin "5") (pinfunction "5_5") (pintype "bidirectional"))
    )
    (net (code "221") (name "unconnected-(U$5-Pad7)") (class "Default")
      (node (ref "U$5") (pin "7") (pinfunction "7_7") (pintype "bidirectional"))
    )
    (net (code "222") (name "unconnected-(U$5-Pad8)") (class "Default")
      (node (ref "U$5") (pin "8") (pinfunction "8_8") (pintype "bidirectional"))
    )
    (net (code "223") (name "unconnected-(U$6-Pad4)") (class "Default")
      (node (ref "U$6") (pin "4") (pinfunction "4_4") (pintype "bidirectional"))
    )
    (net (code "224") (name "unconnected-(U$6-Pad5)") (class "Default")
      (node (ref "U$6") (pin "5") (pinfunction "5_5") (pintype "bidirectional"))
    )
    (net (code "225") (name "unconnected-(U$6-Pad7)") (class "Default")
      (node (ref "U$6") (pin "7") (pinfunction "7_7") (pintype "bidirectional"))
    )
    (net (code "226") (name "unconnected-(U$6-Pad8)") (class "Default")
      (node (ref "U$6") (pin "8") (pinfunction "8_8") (pintype "bidirectional"))
    )
    (net (code "227") (name "unconnected-(U$7-Pad4)") (class "Default")
      (node (ref "U$7") (pin "4") (pinfunction "4_4") (pintype "bidirectional"))
    )
    (net (code "228") (name "unconnected-(U$7-Pad5)") (class "Default")
      (node (ref "U$7") (pin "5") (pinfunction "5_5") (pintype "bidirectional"))
    )
    (net (code "229") (name "unconnected-(U$7-Pad7)") (class "Default")
      (node (ref "U$7") (pin "7") (pinfunction "7_7") (pintype "bidirectional"))
    )
    (net (code "230") (name "unconnected-(U$7-Pad8)") (class "Default")
      (node (ref "U$7") (pin "8") (pinfunction "8_8") (pintype "bidirectional"))
    )
    (net (code "231") (name "unconnected-(U$8-Pad4)") (class "Default")
      (node (ref "U$8") (pin "4") (pinfunction "4_4") (pintype "bidirectional"))
    )
    (net (code "232") (name "unconnected-(U$8-Pad5)") (class "Default")
      (node (ref "U$8") (pin "5") (pinfunction "5_5") (pintype "bidirectional"))
    )
    (net (code "233") (name "unconnected-(U$8-Pad7)") (class "Default")
      (node (ref "U$8") (pin "7") (pinfunction "7_7") (pintype "bidirectional"))
    )
    (net (code "234") (name "unconnected-(U$8-Pad8)") (class "Default")
      (node (ref "U$8") (pin "8") (pinfunction "8_8") (pintype "bidirectional"))
    )
    (net (code "235") (name "unconnected-(U$9-Pad4)") (class "Default")
      (node (ref "U$9") (pin "4") (pinfunction "4_4") (pintype "bidirectional"))
    )
    (net (code "236") (name "unconnected-(U$9-Pad5)") (class "Default")
      (node (ref "U$9") (pin "5") (pinfunction "5_5") (pintype "bidirectional"))
    )
    (net (code "237") (name "unconnected-(U$9-Pad7)") (class "Default")
      (node (ref "U$9") (pin "7") (pinfunction "7_7") (pintype "bidirectional"))
    )
    (net (code "238") (name "unconnected-(U$9-Pad8)") (class "Default")
      (node (ref "U$9") (pin "8") (pinfunction "8_8") (pintype "bidirectional"))
    )
    (net (code "239") (name "unconnected-(U$10-Pad4)") (class "Default")
      (node (ref "U$10") (pin "4") (pinfunction "4_4") (pintype "bidirectional"))
    )
    (net (code "240") (name "unconnected-(U$10-Pad5)") (class "Default")
      (node (ref "U$10") (pin "5") (pinfunction "5_5") (pintype "bidirectional"))
    )
    (net (code "241") (name "unconnected-(U$10-Pad7)") (class "Default")
      (node (ref "U$10") (pin "7") (pinfunction "7_7") (pintype "bidirectional"))
    )
    (net (code "242") (name "unconnected-(U$10-Pad8)") (class "Default")
      (node (ref "U$10") (pin "8") (pinfunction "8_8") (pintype "bidirectional"))
    )
    (net (code "243") (name "unconnected-(U1-A0-Pad31)") (class "Default")
      (node (ref "U1") (pin "31") (pinfunction "A0_31") (pintype "bidirectional"))
    )
    (net (code "244") (name "unconnected-(U1-A1-Pad32)") (class "Default")
      (node (ref "U1") (pin "32") (pinfunction "A1_32") (pintype "bidirectional"))
    )
    (net (code "245") (name "unconnected-(U1-A2-Pad33)") (class "Default")
      (node (ref "U1") (pin "33") (pinfunction "A2_33") (pintype "bidirectional"))
    )
    (net (code "246") (name "unconnected-(U1-A3-Pad34)") (class "Default")
      (node (ref "U1") (pin "34") (pinfunction "A3_34") (pintype "bidirectional"))
    )
    (net (code "247") (name "unconnected-(U1-A4-Pad35)") (class "Default")
      (node (ref "U1") (pin "35") (pinfunction "A4_35") (pintype "bidirectional"))
    )
    (net (code "248") (name "unconnected-(U1-A5-Pad36)") (class "Default")
      (node (ref "U1") (pin "36") (pinfunction "A5_36") (pintype "bidirectional"))
    )
    (net (code "249") (name "unconnected-(U1-A6-Pad37)") (class "Default")
      (node (ref "U1") (pin "37") (pinfunction "A6_37") (pintype "bidirectional"))
    )
    (net (code "250") (name "unconnected-(U1-A7-Pad38)") (class "Default")
      (node (ref "U1") (pin "38") (pinfunction "A7_38") (pintype "bidirectional"))
    )
    (net (code "251") (name "unconnected-(U1-A8-Pad13)") (class "Default")
      (node (ref "U1") (pin "13") (pinfunction "A8_13") (pintype "bidirectional"))
    )
    (net (code "252") (name "unconnected-(U1-A9-Pad14)") (class "Default")
      (node (ref "U1") (pin "14") (pinfunction "A9_14") (pintype "bidirectional"))
    )
    (net (code "253") (name "unconnected-(U1-A10-Pad15)") (class "Default")
      (node (ref "U1") (pin "15") (pinfunction "A10_15") (pintype "bidirectional"))
    )
    (net (code "254") (name "unconnected-(U1-A11-Pad16)") (class "Default")
      (node (ref "U1") (pin "16") (pinfunction "A11_16") (pintype "bidirectional"))
    )
    (net (code "255") (name "unconnected-(U1-A12-Pad17)") (class "Default")
      (node (ref "U1") (pin "17") (pinfunction "A12_17") (pintype "bidirectional"))
    )
    (net (code "256") (name "unconnected-(U1-A13-Pad18)") (class "Default")
      (node (ref "U1") (pin "18") (pinfunction "A13_18") (pintype "bidirectional"))
    )
    (net (code "257") (name "unconnected-(U1-A14-Pad19)") (class "Default")
      (node (ref "U1") (pin "19") (pinfunction "A14_19") (pintype "bidirectional"))
    )
    (net (code "258") (name "unconnected-(U1-D0-Pad4)") (class "Default")
      (node (ref "U1") (pin "4") (pinfunction "D0_4") (pintype "bidirectional"))
    )
    (net (code "259") (name "unconnected-(U1-D1-Pad3)") (class "Default")
      (node (ref "U1") (pin "3") (pinfunction "D1_3") (pintype "bidirectional"))
    )
    (net (code "260") (name "unconnected-(U1-D2-Pad6)") (class "Default")
      (node (ref "U1") (pin "6") (pinfunction "D2_6") (pintype "bidirectional"))
    )
    (net (code "261") (name "unconnected-(U1-D3-Pad5)") (class "Default")
      (node (ref "U1") (pin "5") (pinfunction "D3_5") (pintype "bidirectional"))
    )
    (net (code "262") (name "unconnected-(U1-D4-Pad8)") (class "Default")
      (node (ref "U1") (pin "8") (pinfunction "D4_8") (pintype "bidirectional"))
    )
    (net (code "263") (name "unconnected-(U1-D5-Pad7)") (class "Default")
      (node (ref "U1") (pin "7") (pinfunction "D5_7") (pintype "bidirectional"))
    )
    (net (code "264") (name "unconnected-(U1-D6-Pad10)") (class "Default")
      (node (ref "U1") (pin "10") (pinfunction "D6_10") (pintype "bidirectional"))
    )
    (net (code "265") (name "unconnected-(U1-D7-Pad9)") (class "Default")
      (node (ref "U1") (pin "9") (pinfunction "D7_9") (pintype "bidirectional"))
    )
    (net (code "266") (name "unconnected-(U1-{slash}CS-Pad27)") (class "Default")
      (node (ref "U1") (pin "27") (pinfunction "/CS_27") (pintype "bidirectional"))
    )
    (net (code "267") (name "unconnected-(U1-{slash}RD-Pad26)") (class "Default")
      (node (ref "U1") (pin "26") (pinfunction "/RD_26") (pintype "bidirectional"))
    )
    (net (code "268") (name "unconnected-(U1-{slash}WR-Pad25)") (class "Default")
      (node (ref "U1") (pin "25") (pinfunction "/WR_25") (pintype "bidirectional"))
    )
    (net (code "269") (name "unconnected-(U1_MUX-1Y3-Pad11)") (class "Default")
      (node (ref "U1_MUX") (pin "11") (pinfunction "1Y3_11") (pintype "bidirectional"))
    )
    (net (code "270") (name "unconnected-(U1_MUX-2Y3-Pad4)") (class "Default")
      (node (ref "U1_MUX") (pin "4") (pinfunction "2Y3_4") (pintype "bidirectional"))
    )
    (net (code "271") (name "unconnected-(U2-PB0(ICP)-Pad14)") (class "Default")
      (node (ref "U2") (pin "14") (pinfunction "PB0(ICP)_14") (pintype "bidirectional"))
    )
    (net (code "272") (name "unconnected-(U2-PB1(OC1A)-Pad15)") (class "Default")
      (node (ref "U2") (pin "15") (pinfunction "PB1(OC1A)_15") (pintype "bidirectional"))
    )
    (net (code "273") (name "unconnected-(U2-PB2(SS{slash}OC1B)-Pad16)") (class "Default")
      (node (ref "U2") (pin "16") (pinfunction "PB2(SS/OC1B)_16") (pintype "bidirectional"))
    )
    (net (code "274") (name "unconnected-(U2-PC1(ADC1)-Pad24)") (class "Default")
      (node (ref "U2") (pin "24") (pinfunction "PC1(ADC1)_24") (pintype "bidirectional"))
    )
    (net (code "275") (name "unconnected-(U2-PC2(ADC2)-Pad25)") (class "Default")
      (node (ref "U2") (pin "25") (pinfunction "PC2(ADC2)_25") (pintype "bidirectional"))
    )
    (net (code "276") (name "unconnected-(U2-PC3(ADC3)-Pad26)") (class "Default")
      (node (ref "U2") (pin "26") (pinfunction "PC3(ADC3)_26") (pintype "bidirectional"))
    )
    (net (code "277") (name "unconnected-(U2-PC4(ADC4{slash}SDA)-Pad27)") (class "Default")
      (node (ref "U2") (pin "27") (pinfunction "PC4(ADC4/SDA)_27") (pintype "bidirectional"))
    )
    (net (code "278") (name "unconnected-(U2-PC5(ADC5{slash}SCL)-Pad28)") (class "Default")
      (node (ref "U2") (pin "28") (pinfunction "PC5(ADC5/SCL)_28") (pintype "bidirectional"))
    )
    (net (code "279") (name "unconnected-(U2_MUX-1Y3-Pad11)") (class "Default")
      (node (ref "U2_MUX") (pin "11") (pinfunction "1Y3_11") (pintype "bidirectional"))
    )
    (net (code "280") (name "unconnected-(U2_MUX-2Y3-Pad4)") (class "Default")
      (node (ref "U2_MUX") (pin "4") (pinfunction "2Y3_4") (pintype "bidirectional"))
    )
    (net (code "281") (name "unconnected-(U3_MUX-1Y3-Pad11)") (class "Default")
      (node (ref "U3_MUX") (pin "11") (pinfunction "1Y3_11") (pintype "bidirectional"))
    )
    (net (code "282") (name "unconnected-(U3_MUX-2Y3-Pad4)") (class "Default")
      (node (ref "U3_MUX") (pin "4") (pinfunction "2Y3_4") (pintype "bidirectional"))
    )
    (net (code "283") (name "unconnected-(U4_MUX-1Y3-Pad11)") (class "Default")
      (node (ref "U4_MUX") (pin "11") (pinfunction "1Y3_11") (pintype "bidirectional"))
    )
    (net (code "284") (name "unconnected-(U4_MUX-2Y3-Pad4)") (class "Default")
      (node (ref "U4_MUX") (pin "4") (pinfunction "2Y3_4") (pintype "bidirectional"))
    )
    (net (code "285") (name "unconnected-(U7_MUX-1Y3-Pad11)") (class "Default")
      (node (ref "U7_MUX") (pin "11") (pinfunction "1Y3_11") (pintype "bidirectional"))
    )
    (net (code "286") (name "unconnected-(U7_MUX-2Y3-Pad4)") (class "Default")
      (node (ref "U7_MUX") (pin "4") (pinfunction "2Y3_4") (pintype "bidirectional"))
    )
  )
)
